# swift-nav.net
KiCad netlist of a schematic drawn in EAGLE
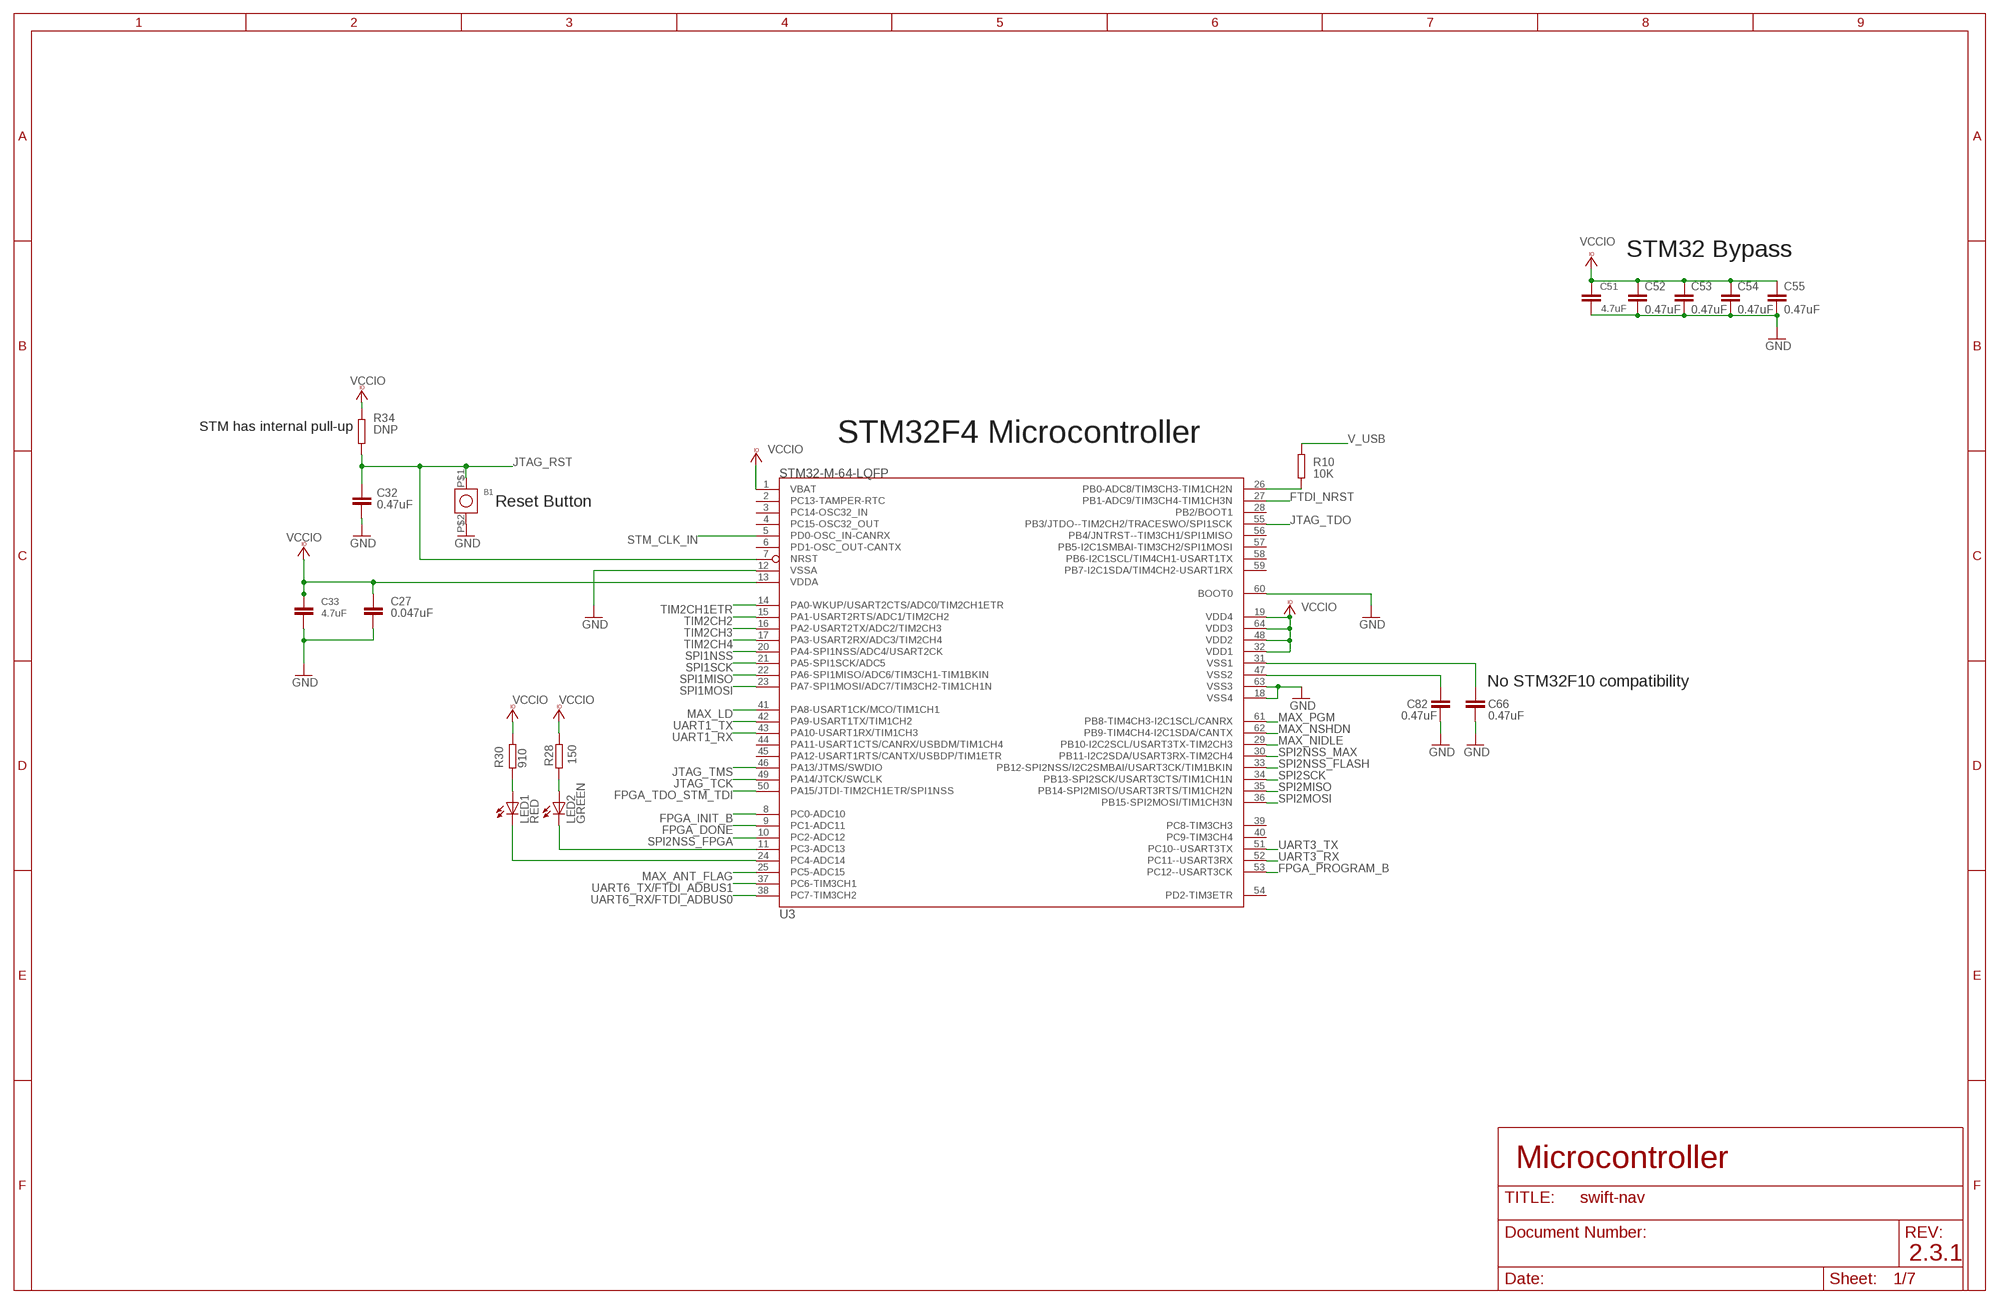
[diagram p0: schematic, sheet 1]
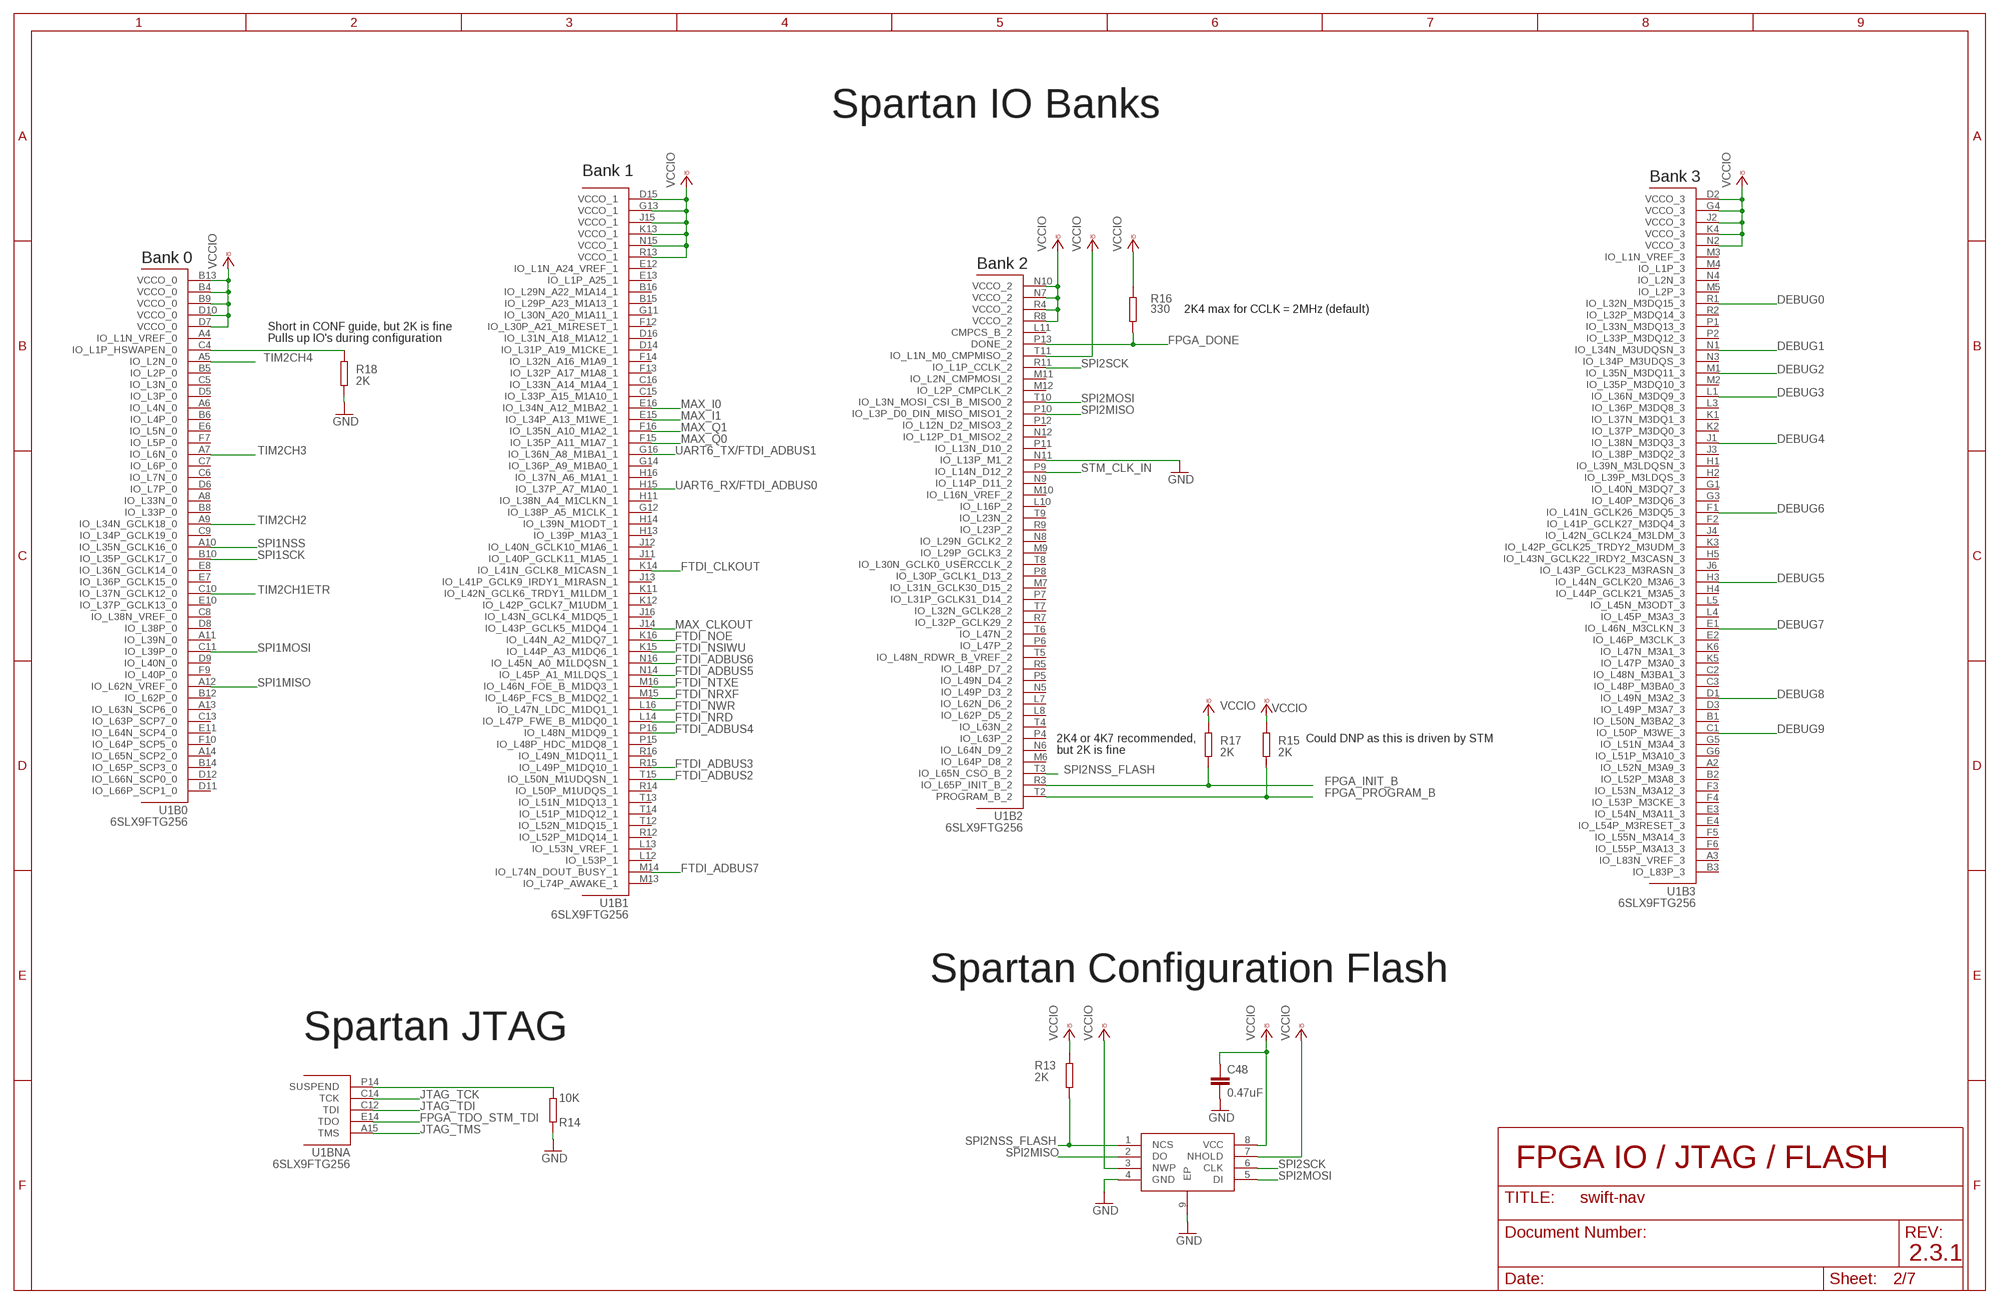
[diagram p1: schematic, sheet 2]
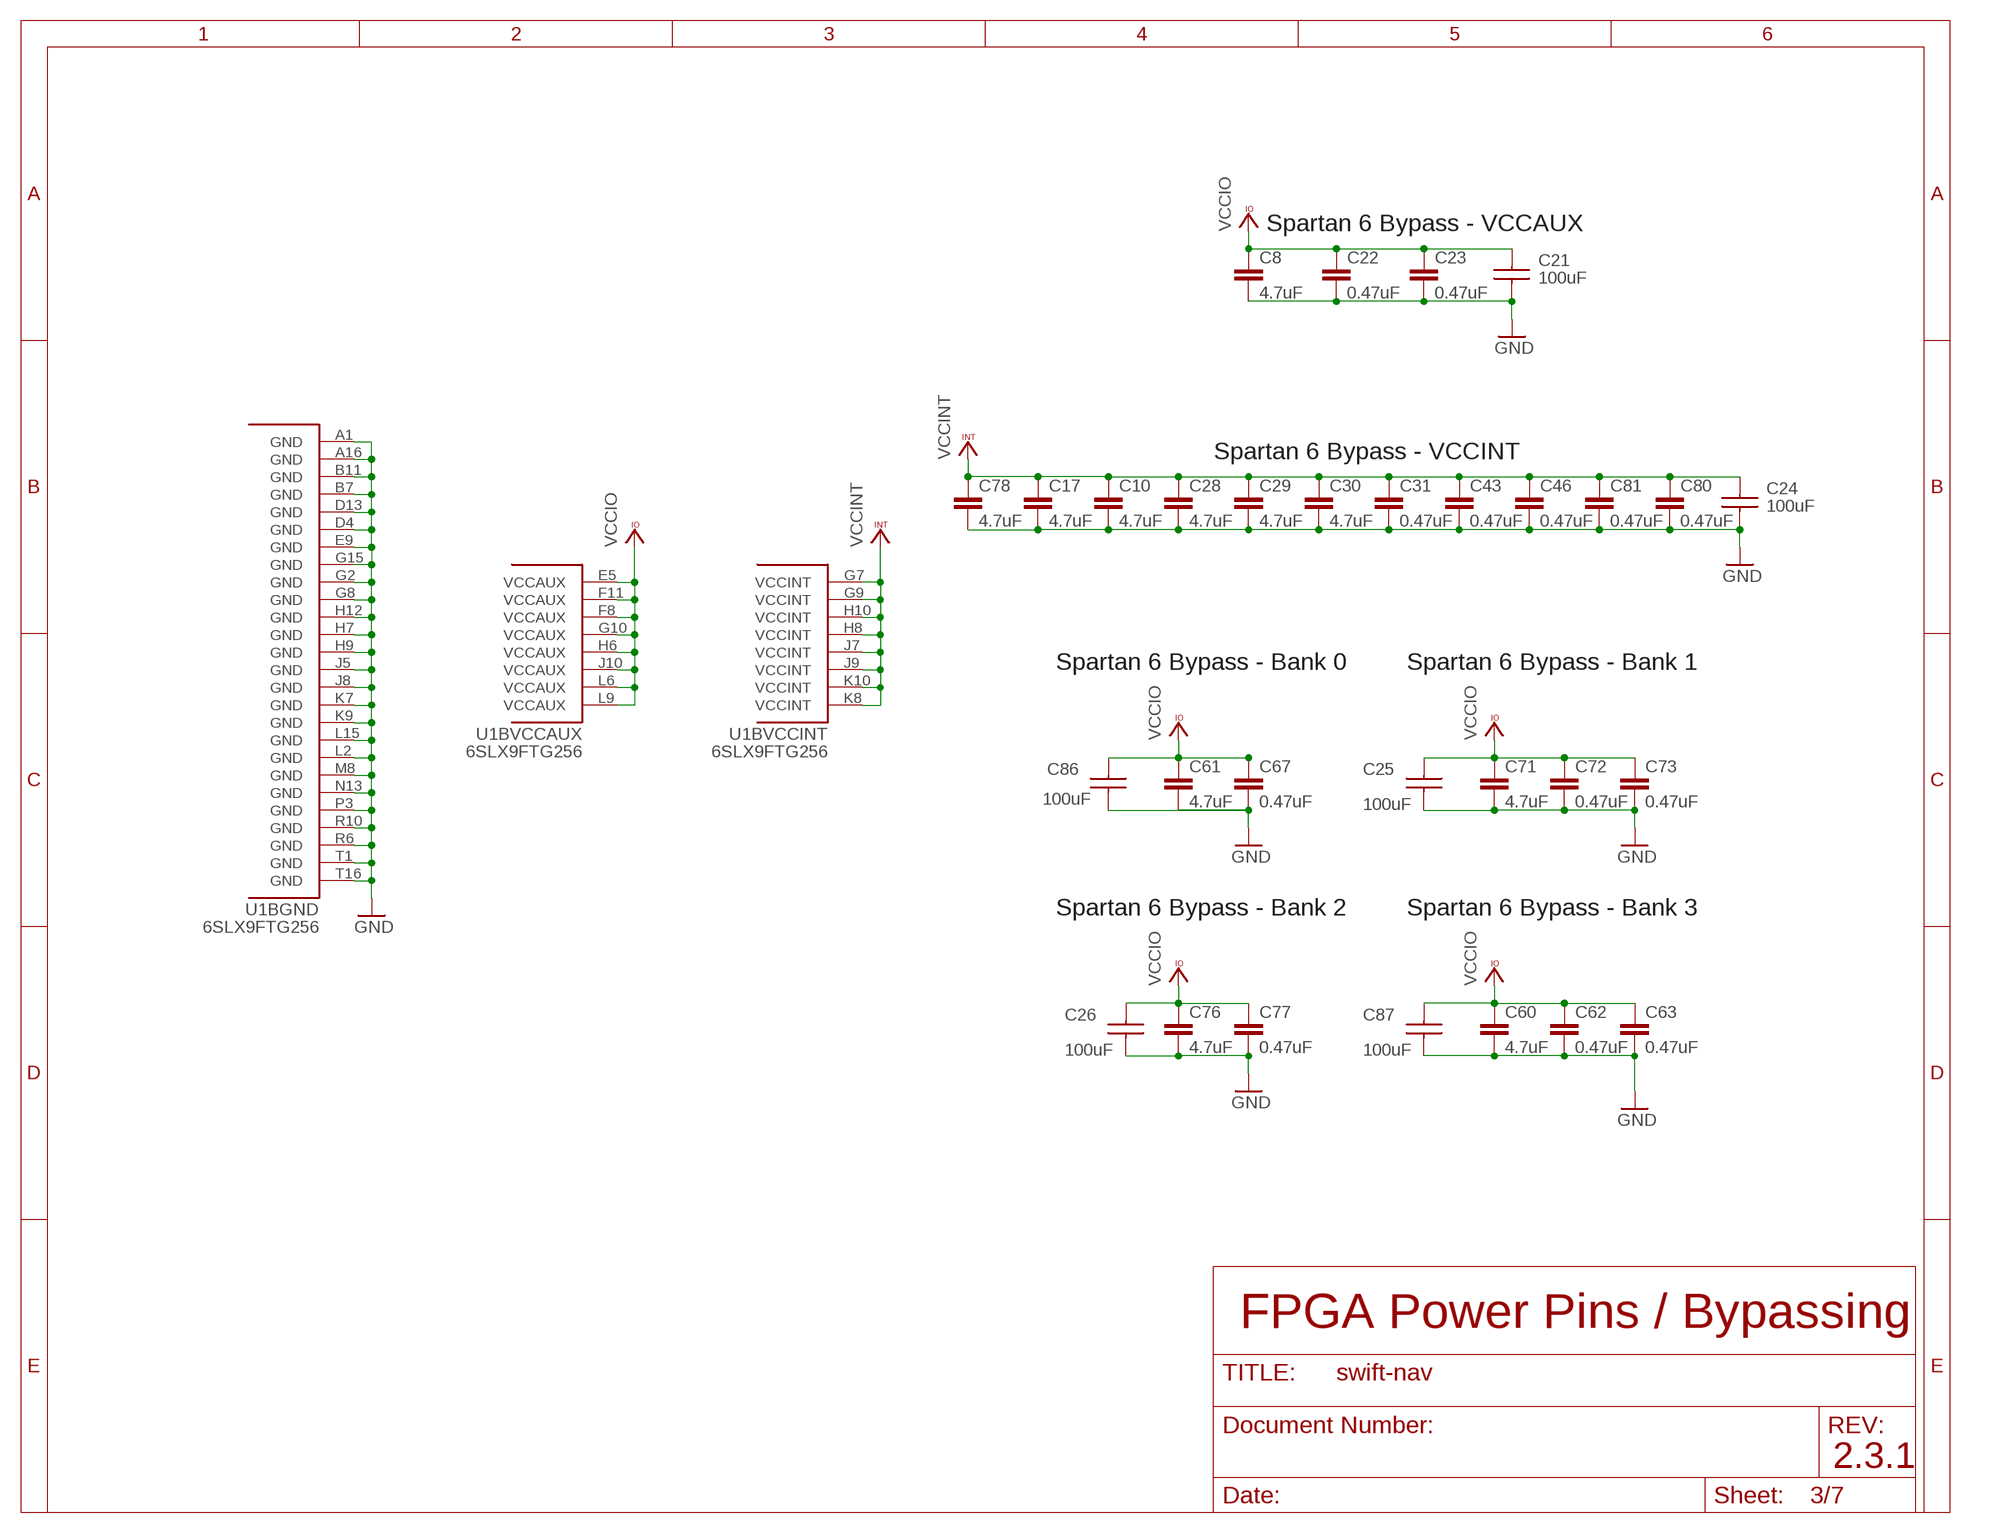
[diagram p2: schematic, sheet 3]
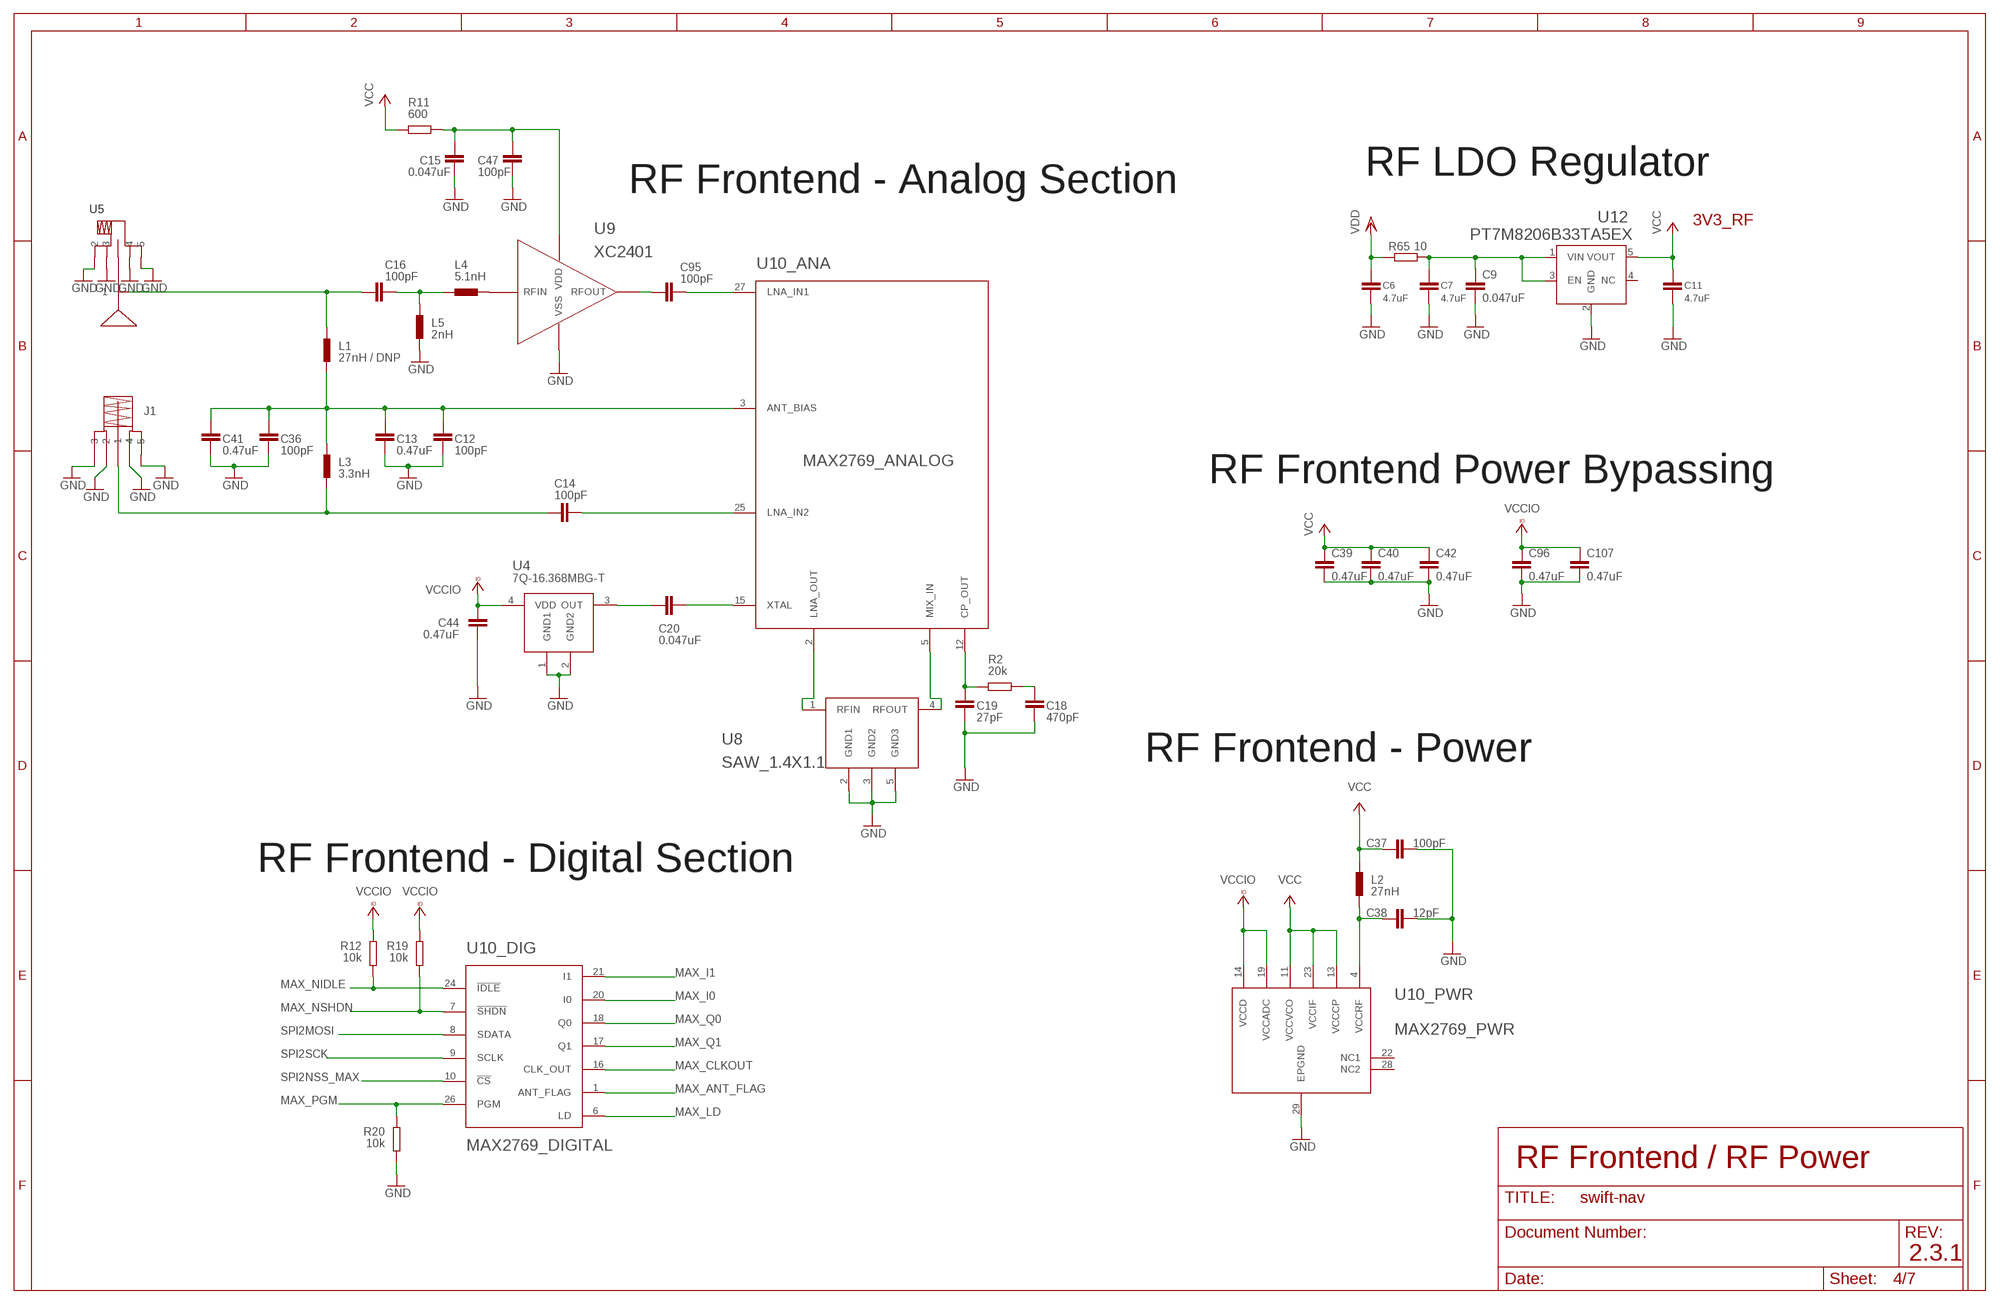
[diagram p3: schematic, sheet 4]
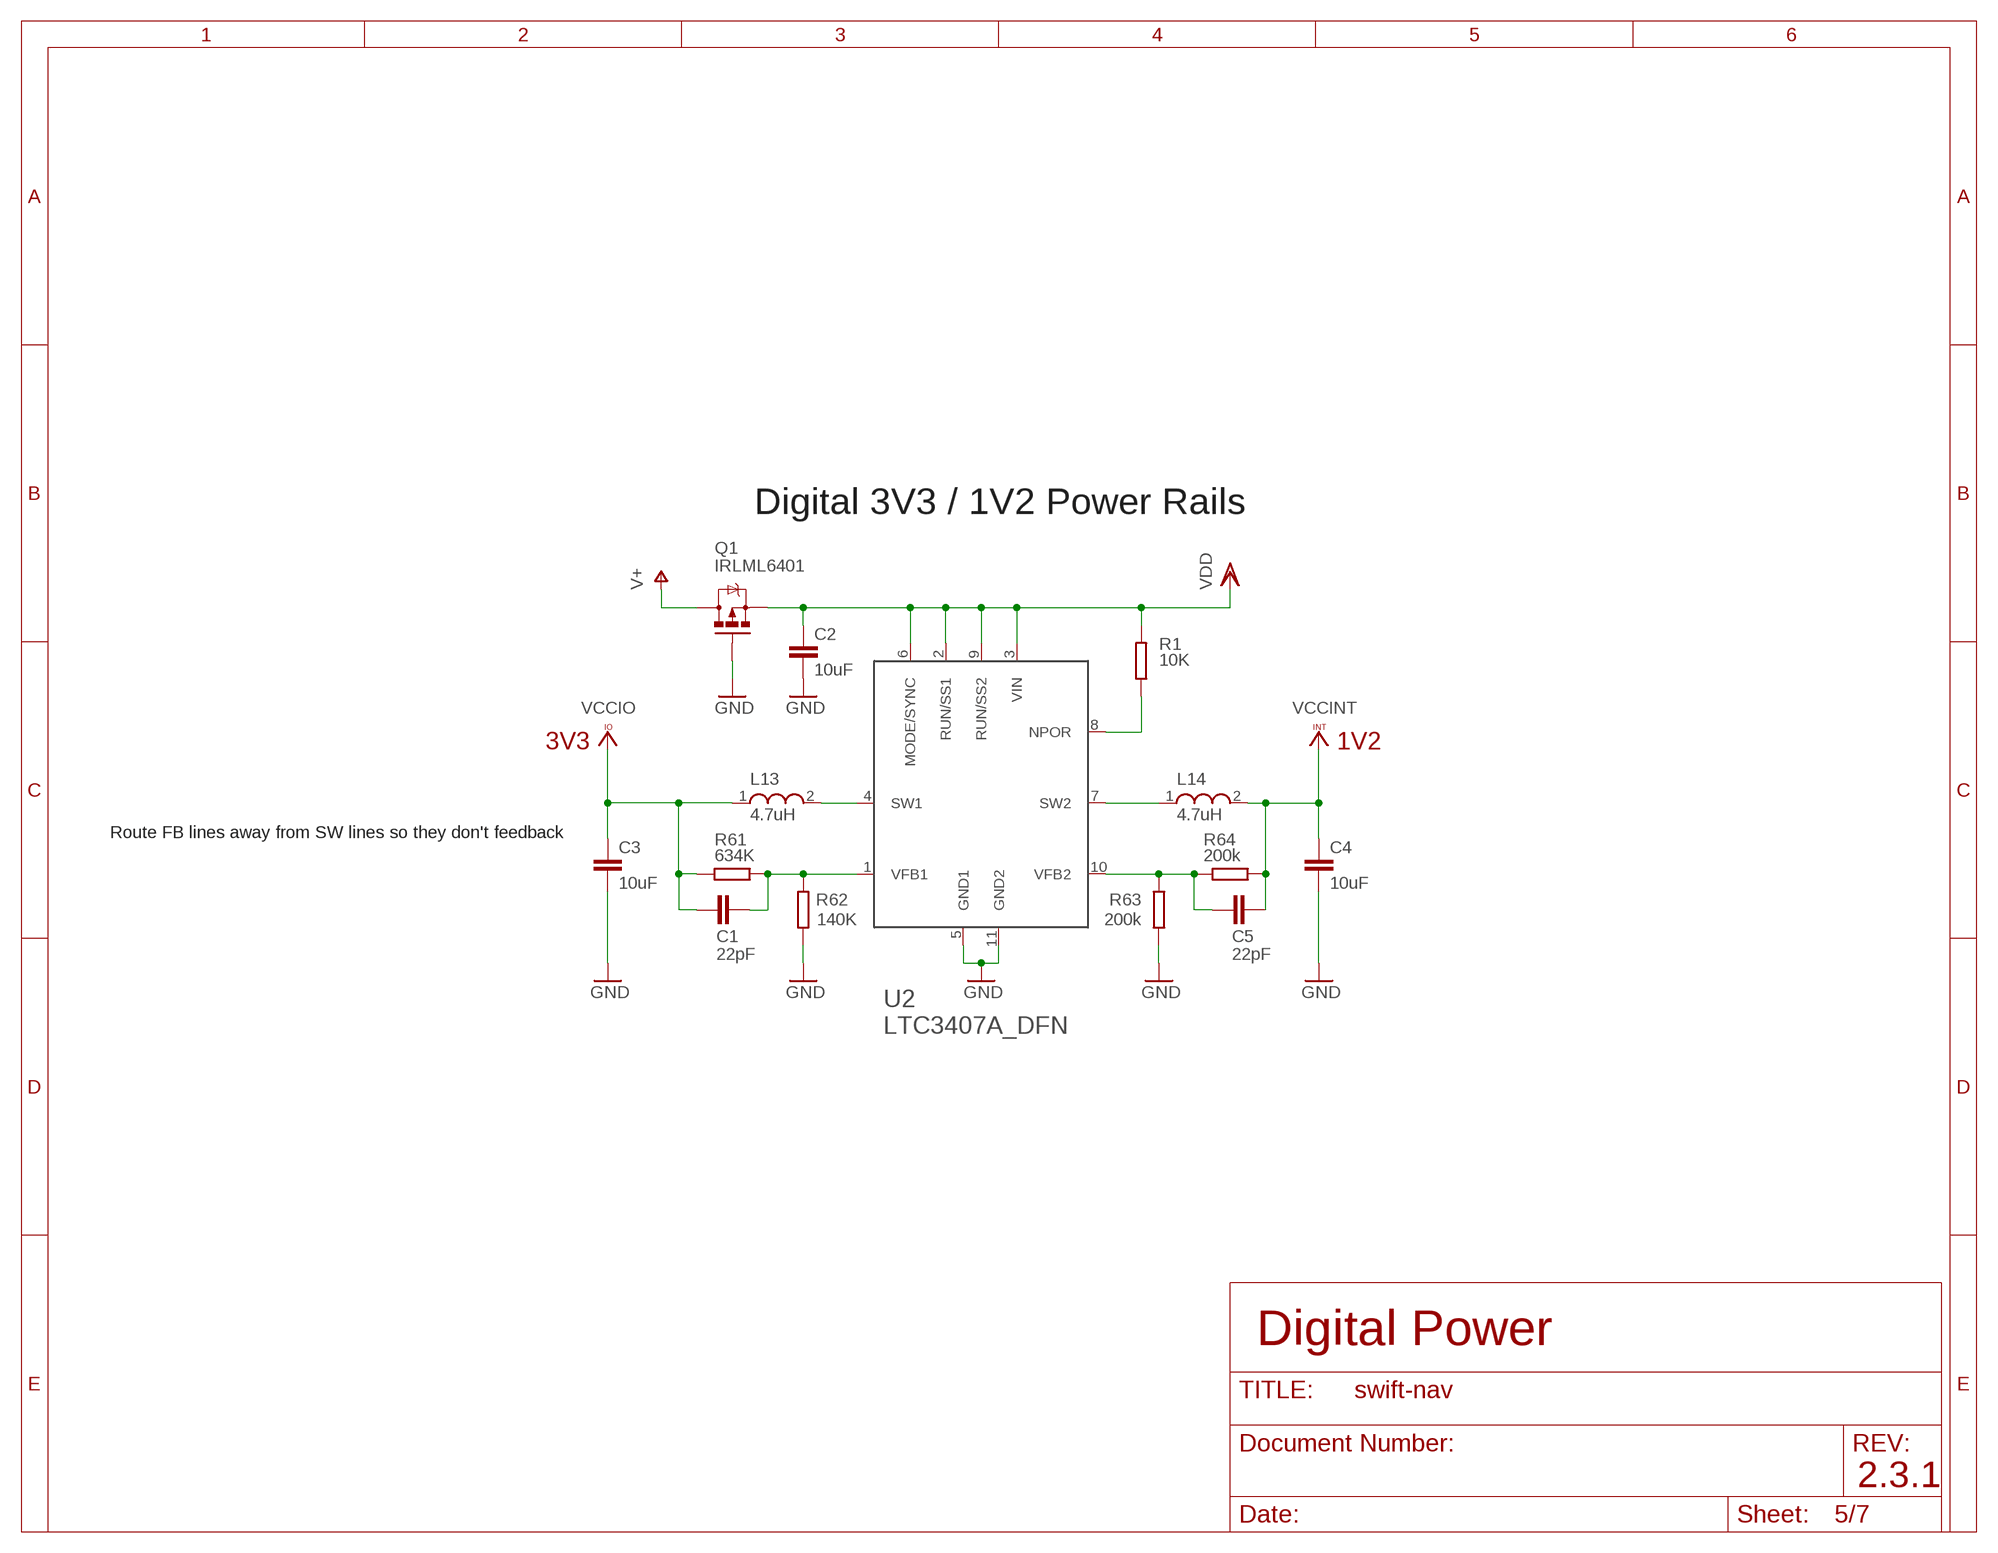
[diagram p4: schematic, sheet 5]
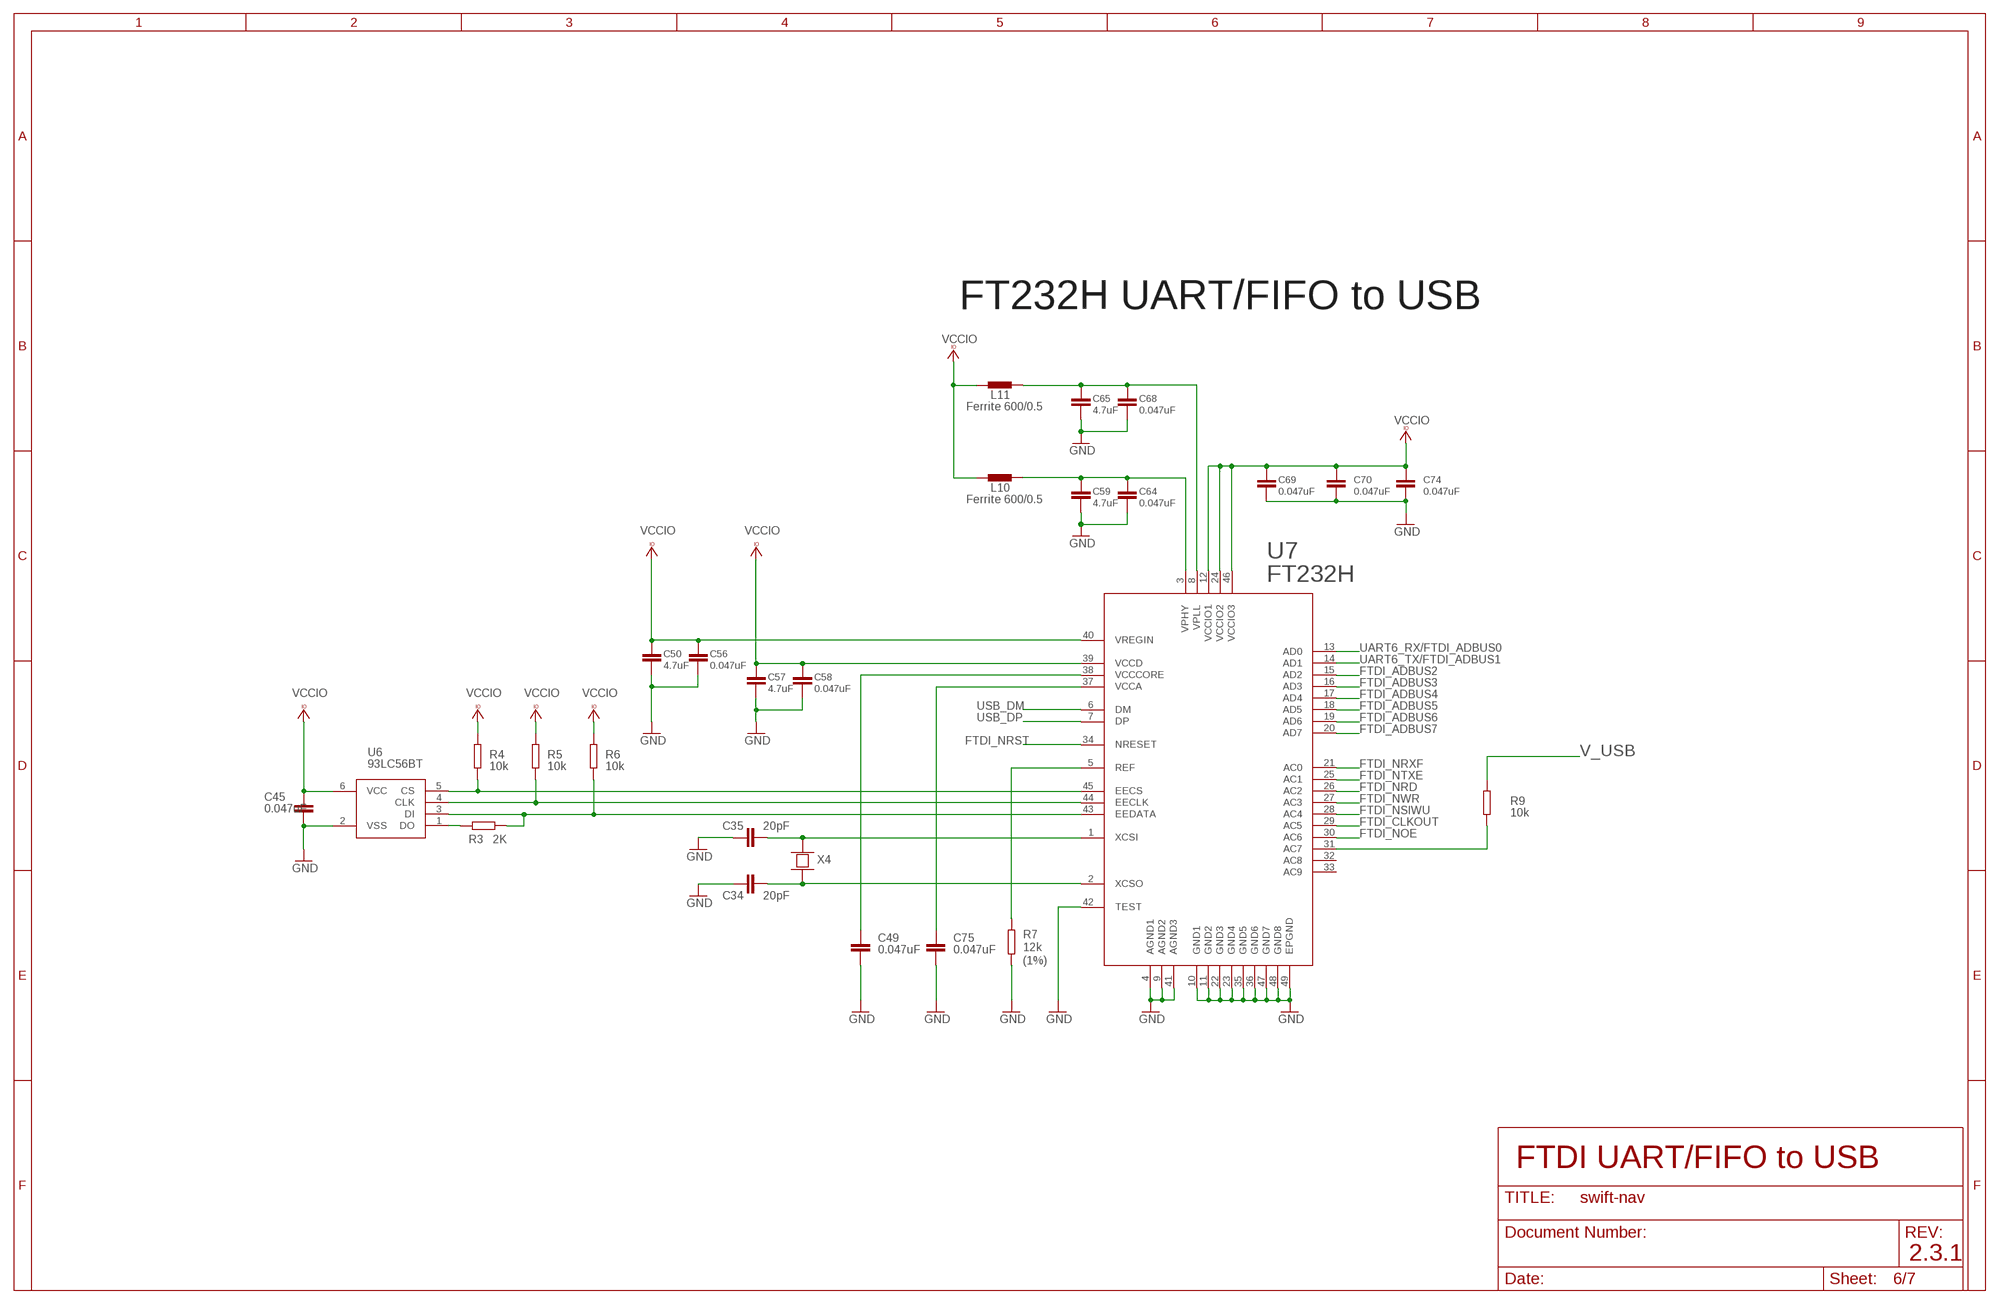
[diagram p5: schematic, sheet 6]
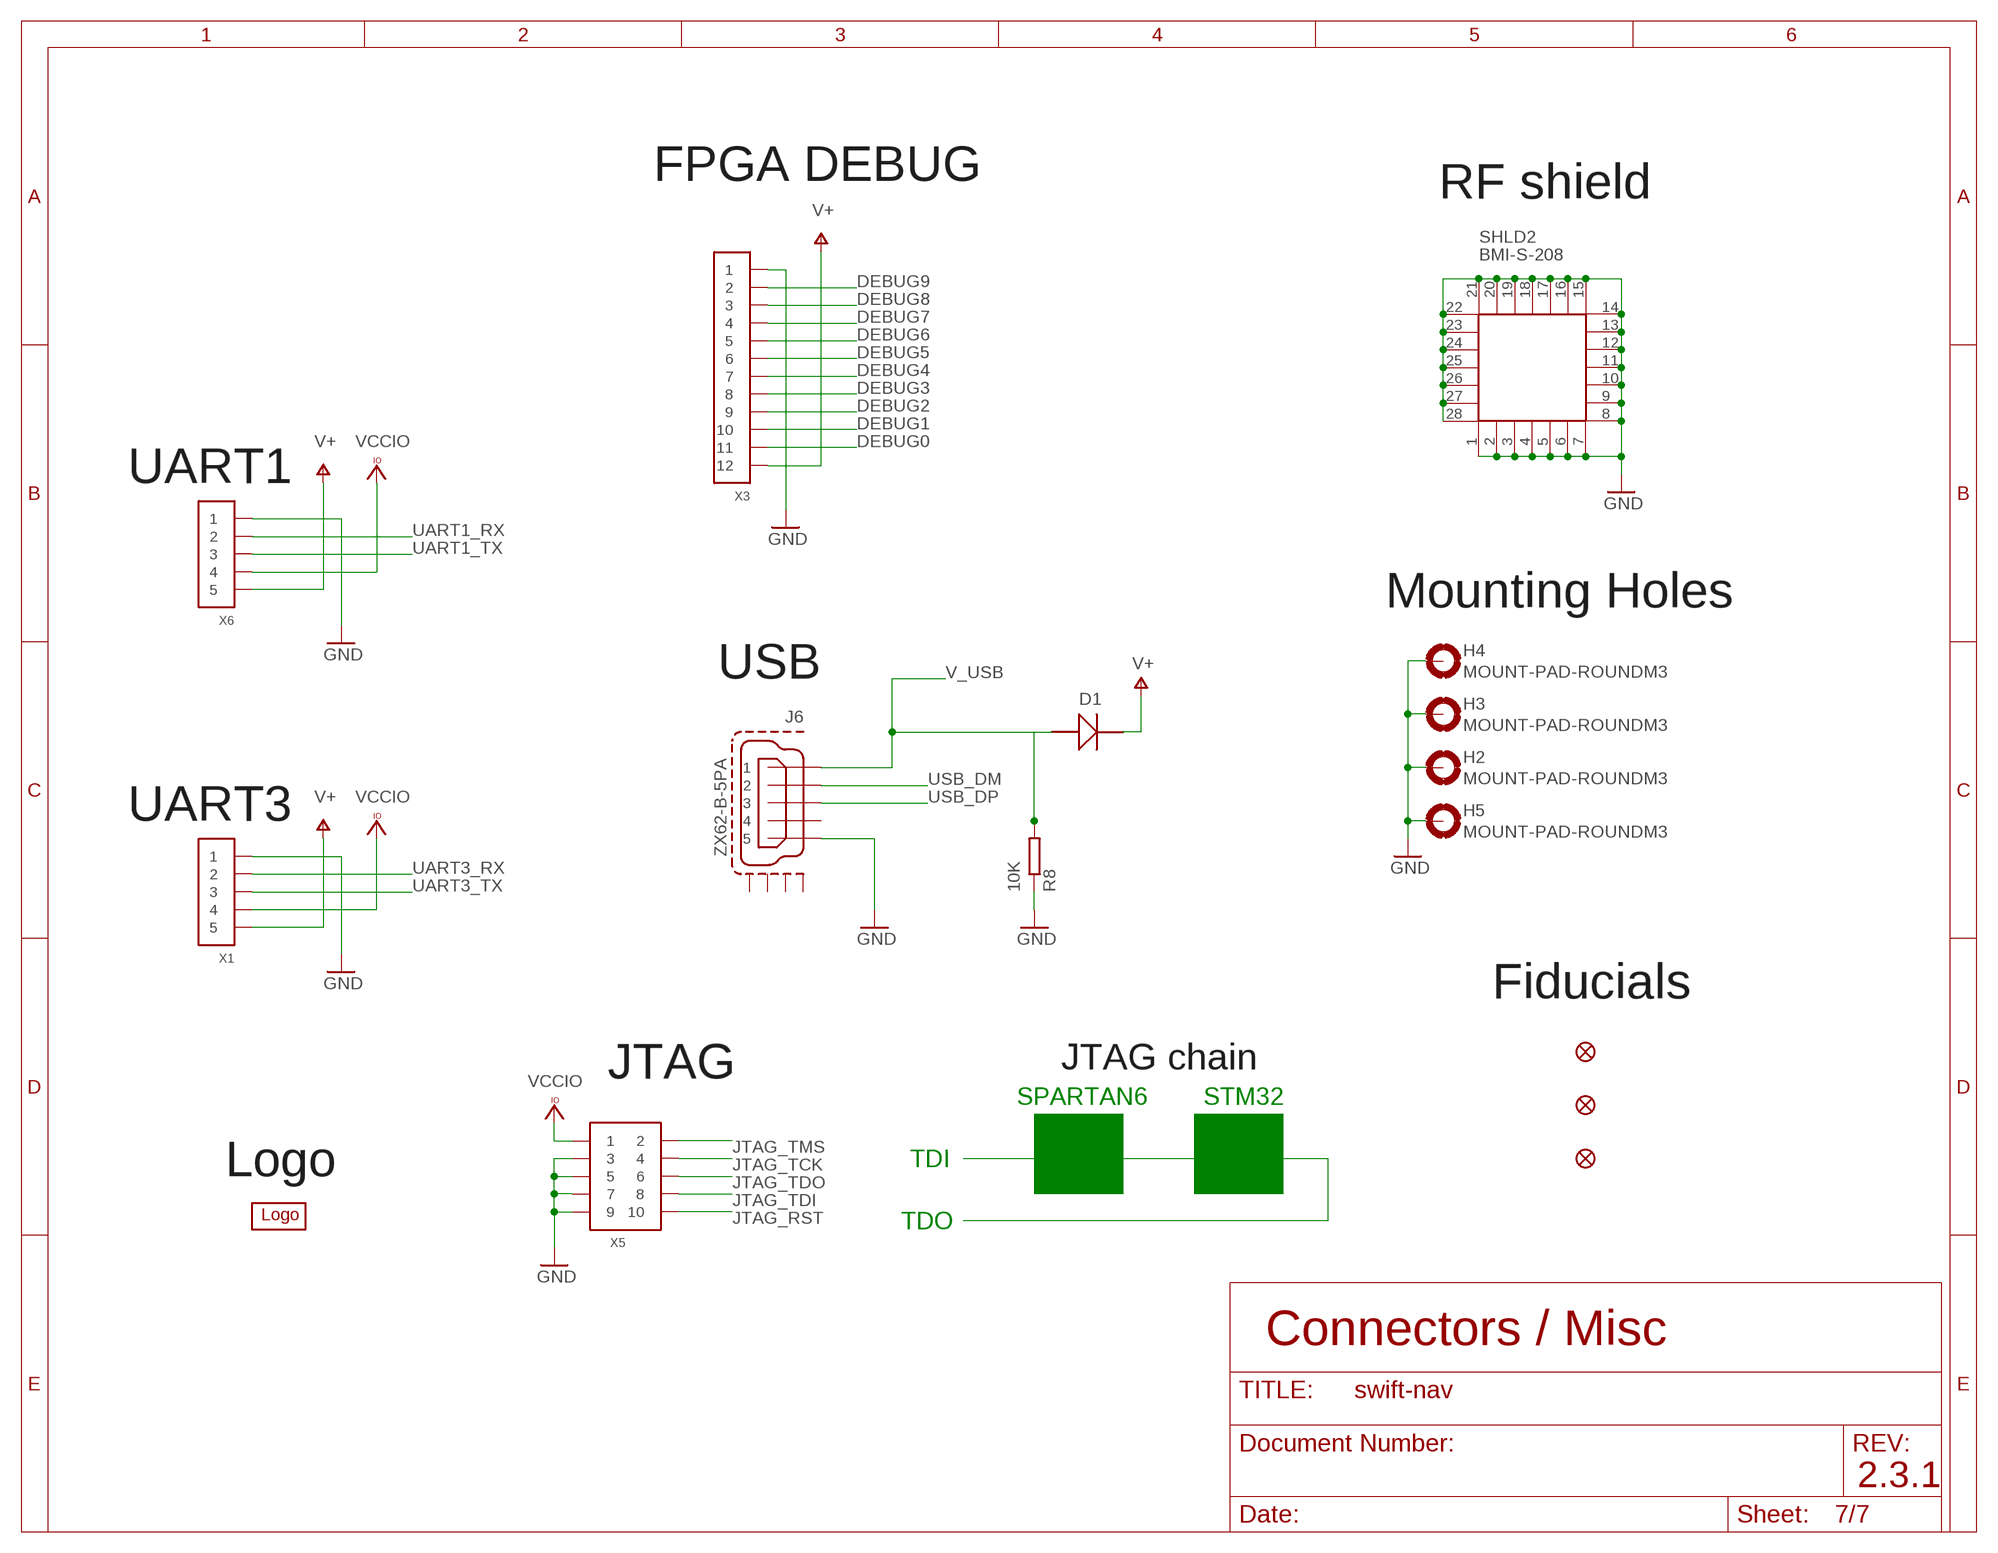
[diagram p6: schematic, sheet 7]

(export (version "E")
  (design (tool "Eeschema 10.0.6"))
  (components
    (comp (ref "C8")
      (value "4.7uF")
      (footprint "eagle-import:0603-CAP")
      (libsource (lib "eagle-import") (part "CAPACITOR-0603"))
    )
    (comp (ref "C10")
      (value "4.7uF")
      (footprint "eagle-import:0603-CAP")
      (libsource (lib "eagle-import") (part "CAPACITOR-0603"))
    )
    (comp (ref "C17")
      (value "4.7uF")
      (footprint "eagle-import:0603-CAP")
      (libsource (lib "eagle-import") (part "CAPACITOR-0603"))
    )
    (comp (ref "C21")
      (value "100uF")
      (footprint "eagle-import:C1210")
      (libsource (lib "eagle-import") (part "C1210"))
    )
    (comp (ref "C22")
      (value "0.47uF")
      (footprint "eagle-import:0402-CAP")
      (libsource (lib "eagle-import") (part "CAPACITOR-0402"))
    )
    (comp (ref "C23")
      (value "0.47uF")
      (footprint "eagle-import:0402-CAP")
      (libsource (lib "eagle-import") (part "CAPACITOR-0402"))
    )
    (comp (ref "C24")
      (value "100uF")
      (footprint "eagle-import:C1210")
      (libsource (lib "eagle-import") (part "C1210"))
    )
    (comp (ref "C25")
      (value "100uF")
      (footprint "eagle-import:C1210")
      (libsource (lib "eagle-import") (part "C1210"))
    )
    (comp (ref "C26")
      (value "100uF")
      (footprint "eagle-import:C1210")
      (libsource (lib "eagle-import") (part "C1210"))
    )
    (comp (ref "C28")
      (value "4.7uF")
      (footprint "eagle-import:0603-CAP")
      (libsource (lib "eagle-import") (part "CAPACITOR-0603"))
    )
    (comp (ref "C29")
      (value "4.7uF")
      (footprint "eagle-import:0603-CAP")
      (libsource (lib "eagle-import") (part "CAPACITOR-0603"))
    )
    (comp (ref "C30")
      (value "4.7uF")
      (footprint "eagle-import:0603-CAP")
      (libsource (lib "eagle-import") (part "CAPACITOR-0603"))
    )
    (comp (ref "C31")
      (value "0.47uF")
      (footprint "eagle-import:0402-CAP")
      (libsource (lib "eagle-import") (part "CAPACITOR-0402"))
    )
    (comp (ref "C43")
      (value "0.47uF")
      (footprint "eagle-import:0402-CAP")
      (libsource (lib "eagle-import") (part "CAPACITOR-0402"))
    )
    (comp (ref "C46")
      (value "0.47uF")
      (footprint "eagle-import:0402-CAP")
      (libsource (lib "eagle-import") (part "CAPACITOR-0402"))
    )
    (comp (ref "C60")
      (value "4.7uF")
      (footprint "eagle-import:0603-CAP")
      (libsource (lib "eagle-import") (part "CAPACITOR-0603"))
    )
    (comp (ref "C61")
      (value "4.7uF")
      (footprint "eagle-import:0603-CAP")
      (libsource (lib "eagle-import") (part "CAPACITOR-0603"))
    )
    (comp (ref "C62")
      (value "0.47uF")
      (footprint "eagle-import:0402-CAP")
      (libsource (lib "eagle-import") (part "CAPACITOR-0402"))
    )
    (comp (ref "C63")
      (value "0.47uF")
      (footprint "eagle-import:0402-CAP")
      (libsource (lib "eagle-import") (part "CAPACITOR-0402"))
    )
    (comp (ref "C67")
      (value "0.47uF")
      (footprint "eagle-import:0402-CAP")
      (libsource (lib "eagle-import") (part "CAPACITOR-0402"))
    )
    (comp (ref "C71")
      (value "4.7uF")
      (footprint "eagle-import:0603-CAP")
      (libsource (lib "eagle-import") (part "CAPACITOR-0603"))
    )
    (comp (ref "C72")
      (value "0.47uF")
      (footprint "eagle-import:0402-CAP")
      (libsource (lib "eagle-import") (part "CAPACITOR-0402"))
    )
    (comp (ref "C73")
      (value "0.47uF")
      (footprint "eagle-import:0402-CAP")
      (libsource (lib "eagle-import") (part "CAPACITOR-0402"))
    )
    (comp (ref "C76")
      (value "4.7uF")
      (footprint "eagle-import:0603-CAP")
      (libsource (lib "eagle-import") (part "CAPACITOR-0603"))
    )
    (comp (ref "C77")
      (value "0.47uF")
      (footprint "eagle-import:0402-CAP")
      (libsource (lib "eagle-import") (part "CAPACITOR-0402"))
    )
    (comp (ref "C78")
      (value "4.7uF")
      (footprint "eagle-import:0603-CAP")
      (libsource (lib "eagle-import") (part "CAPACITOR-0603"))
    )
    (comp (ref "C80")
      (value "0.47uF")
      (footprint "eagle-import:0402-CAP")
      (libsource (lib "eagle-import") (part "CAPACITOR-0402"))
    )
    (comp (ref "C81")
      (value "0.47uF")
      (footprint "eagle-import:0402-CAP")
      (libsource (lib "eagle-import") (part "CAPACITOR-0402"))
    )
    (comp (ref "C86")
      (value "100uF")
      (footprint "eagle-import:C1210")
      (libsource (lib "eagle-import") (part "C1210"))
    )
    (comp (ref "C87")
      (value "100uF")
      (footprint "eagle-import:C1210")
      (libsource (lib "eagle-import") (part "C1210"))
    )
    (comp (ref "U1")
      (value "6SLX9FTG256")
      (footprint "eagle-import:FT256")
      (libsource (lib "eagle-import") (part "6SLX9FTG256"))
    )
    (comp (ref "C6")
      (value "4.7uF")
      (footprint "eagle-import:0603-CAP")
      (libsource (lib "eagle-import") (part "CAPACITOR-0603"))
    )
    (comp (ref "C7")
      (value "4.7uF")
      (footprint "eagle-import:0603-CAP")
      (libsource (lib "eagle-import") (part "CAPACITOR-0603"))
    )
    (comp (ref "C9")
      (value "0.047uF")
      (footprint "eagle-import:0402-CAP")
      (libsource (lib "eagle-import") (part "CAPACITOR-0402"))
    )
    (comp (ref "C11")
      (value "4.7uF")
      (footprint "eagle-import:0603-CAP")
      (libsource (lib "eagle-import") (part "CAPACITOR-0603"))
    )
    (comp (ref "C12")
      (value "100pF")
      (footprint "eagle-import:0402-CAP")
      (libsource (lib "eagle-import") (part "CAPACITOR-0402"))
    )
    (comp (ref "C13")
      (value "0.47uF")
      (footprint "eagle-import:0402-CAP")
      (libsource (lib "eagle-import") (part "CAPACITOR-0402"))
    )
    (comp (ref "C14")
      (value "100pF")
      (footprint "eagle-import:0402-CAP")
      (libsource (lib "eagle-import") (part "CAPACITOR-0402"))
    )
    (comp (ref "C15")
      (value "0.047uF")
      (footprint "eagle-import:0402-CAP")
      (libsource (lib "eagle-import") (part "CAPACITOR-0402"))
    )
    (comp (ref "C16")
      (value "100pF")
      (footprint "eagle-import:0402-CAP")
      (libsource (lib "eagle-import") (part "CAPACITOR-0402"))
    )
    (comp (ref "C18")
      (value "470pF")
      (footprint "eagle-import:0402-CAP")
      (libsource (lib "eagle-import") (part "CAPACITOR-0402"))
    )
    (comp (ref "C19")
      (value "27pF")
      (footprint "eagle-import:0402-CAP")
      (libsource (lib "eagle-import") (part "CAPACITOR-0402"))
    )
    (comp (ref "C20")
      (value "0.047uF")
      (footprint "eagle-import:0402-CAP")
      (libsource (lib "eagle-import") (part "CAPACITOR-0402"))
    )
    (comp (ref "C36")
      (value "100pF")
      (footprint "eagle-import:0402-CAP")
      (libsource (lib "eagle-import") (part "CAPACITOR-0402"))
    )
    (comp (ref "C37")
      (value "100pF")
      (footprint "eagle-import:0402-CAP")
      (libsource (lib "eagle-import") (part "CAPACITOR-0402"))
    )
    (comp (ref "C38")
      (value "12pF")
      (footprint "eagle-import:0402-CAP")
      (libsource (lib "eagle-import") (part "CAPACITOR-0402"))
    )
    (comp (ref "C39")
      (value "0.47uF")
      (footprint "eagle-import:0402-CAP")
      (libsource (lib "eagle-import") (part "CAPACITOR-0402"))
    )
    (comp (ref "C40")
      (value "0.47uF")
      (footprint "eagle-import:0402-CAP")
      (libsource (lib "eagle-import") (part "CAPACITOR-0402"))
    )
    (comp (ref "C41")
      (value "0.47uF")
      (footprint "eagle-import:0402-CAP")
      (libsource (lib "eagle-import") (part "CAPACITOR-0402"))
    )
    (comp (ref "C42")
      (value "0.47uF")
      (footprint "eagle-import:0402-CAP")
      (libsource (lib "eagle-import") (part "CAPACITOR-0402"))
    )
    (comp (ref "C44")
      (value "0.47uF")
      (footprint "eagle-import:0402-CAP")
      (libsource (lib "eagle-import") (part "CAPACITOR-0402"))
    )
    (comp (ref "C47")
      (value "100pF")
      (footprint "eagle-import:0402-CAP")
      (libsource (lib "eagle-import") (part "CAPACITOR-0402"))
    )
    (comp (ref "C95")
      (value "100pF")
      (footprint "eagle-import:0402-CAP")
      (libsource (lib "eagle-import") (part "CAPACITOR-0402"))
    )
    (comp (ref "C96")
      (value "0.47uF")
      (footprint "eagle-import:0402-CAP")
      (libsource (lib "eagle-import") (part "CAPACITOR-0402"))
    )
    (comp (ref "C107")
      (value "0.47uF")
      (footprint "eagle-import:0402-CAP")
      (libsource (lib "eagle-import") (part "CAPACITOR-0402"))
    )
    (comp (ref "J1")
      (value "SMA_EDGE")
      (footprint "eagle-import:SMA_EDGE")
      (libsource (lib "eagle-import") (part "SMA_EDGE"))
    )
    (comp (ref "L1")
      (value "27nH / DNP")
      (footprint "eagle-import:0402-IND")
      (libsource (lib "eagle-import") (part "INDUCTOR-0402"))
    )
    (comp (ref "L2")
      (value "27nH")
      (footprint "eagle-import:0402-IND")
      (libsource (lib "eagle-import") (part "INDUCTOR-0402"))
    )
    (comp (ref "L3")
      (value "3.3nH")
      (footprint "eagle-import:0402-IND")
      (libsource (lib "eagle-import") (part "INDUCTOR-0402"))
    )
    (comp (ref "L4")
      (value "5.1nH")
      (footprint "eagle-import:0402-IND")
      (libsource (lib "eagle-import") (part "INDUCTOR-0402"))
    )
    (comp (ref "L5")
      (value "2nH")
      (footprint "eagle-import:0402-IND")
      (libsource (lib "eagle-import") (part "INDUCTOR-0402"))
    )
    (comp (ref "R2")
      (value "20k")
      (footprint "eagle-import:0402-RES")
      (libsource (lib "eagle-import") (part "RESISTOR-0402"))
    )
    (comp (ref "R11")
      (value "600")
      (footprint "eagle-import:0402-RES")
      (libsource (lib "eagle-import") (part "RESISTOR-0402"))
    )
    (comp (ref "R12")
      (value "10k")
      (footprint "eagle-import:0402-RES")
      (libsource (lib "eagle-import") (part "RESISTOR-0402"))
    )
    (comp (ref "R19")
      (value "10k")
      (footprint "eagle-import:0402-RES")
      (libsource (lib "eagle-import") (part "RESISTOR-0402"))
    )
    (comp (ref "R20")
      (value "10k")
      (footprint "eagle-import:0402-RES")
      (libsource (lib "eagle-import") (part "RESISTOR-0402"))
    )
    (comp (ref "R65")
      (value "10")
      (footprint "eagle-import:0402-RES")
      (libsource (lib "eagle-import") (part "RESISTOR-0402"))
    )
    (comp (ref "U4")
      (value "7Q-16.368MBG-T")
      (footprint "eagle-import:TCX_7Q")
      (libsource (lib "eagle-import") (part "7Q-16.368MBG-T"))
    )
    (comp (ref "U5")
      (value "SMA_PATCH_SMDGND")
      (footprint "eagle-import:SMA_PATCH_SMDGND")
      (libsource (lib "eagle-import") (part "SMA_PATCH_SMDGND"))
    )
    (comp (ref "U8")
      (value "SAW_1.4X1.1")
      (footprint "eagle-import:SAW_1.4X1.1")
      (libsource (lib "eagle-import") (part "SAW_1.4X1.1"))
    )
    (comp (ref "U9")
      (value "XC2401")
      (footprint "eagle-import:XC2401")
      (libsource (lib "eagle-import") (part "XC2401"))
    )
    (comp (ref "U10")
      (value "MAX2769")
      (footprint "eagle-import:MAX2769")
      (libsource (lib "eagle-import") (part "MAX2769"))
    )
    (comp (ref "U12")
      (value "PT7M8206B33TA5EX")
      (footprint "eagle-import:PT7M8206B33TA5EX")
      (libsource (lib "eagle-import") (part "PT7M8206B33TA5EX"))
    )
    (comp (ref "B1")
      (value "B3U-1000P")
      (footprint "eagle-import:B3U-1000P")
      (libsource (lib "eagle-import") (part "B3U-1000P"))
    )
    (comp (ref "C27")
      (value "0.047uF")
      (footprint "eagle-import:0402-CAP")
      (libsource (lib "eagle-import") (part "CAPACITOR-0402"))
    )
    (comp (ref "C32")
      (value "0.47uF")
      (footprint "eagle-import:0402-CAP")
      (libsource (lib "eagle-import") (part "CAPACITOR-0402"))
    )
    (comp (ref "C33")
      (value "4.7uF")
      (footprint "eagle-import:0603-CAP")
      (libsource (lib "eagle-import") (part "CAPACITOR-0603"))
    )
    (comp (ref "C51")
      (value "4.7uF")
      (footprint "eagle-import:0603-CAP")
      (libsource (lib "eagle-import") (part "CAPACITOR-0603"))
    )
    (comp (ref "C52")
      (value "0.47uF")
      (footprint "eagle-import:0402-CAP")
      (libsource (lib "eagle-import") (part "CAPACITOR-0402"))
    )
    (comp (ref "C53")
      (value "0.47uF")
      (footprint "eagle-import:0402-CAP")
      (libsource (lib "eagle-import") (part "CAPACITOR-0402"))
    )
    (comp (ref "C54")
      (value "0.47uF")
      (footprint "eagle-import:0402-CAP")
      (libsource (lib "eagle-import") (part "CAPACITOR-0402"))
    )
    (comp (ref "C55")
      (value "0.47uF")
      (footprint "eagle-import:0402-CAP")
      (libsource (lib "eagle-import") (part "CAPACITOR-0402"))
    )
    (comp (ref "C66")
      (value "0.47uF")
      (footprint "eagle-import:0402-CAP")
      (libsource (lib "eagle-import") (part "CAPACITOR-0402"))
    )
    (comp (ref "C82")
      (value "0.47uF")
      (footprint "eagle-import:0402-CAP")
      (libsource (lib "eagle-import") (part "CAPACITOR-0402"))
    )
    (comp (ref "LED1")
      (value "RED")
      (footprint "eagle-import:0603-LED")
      (libsource (lib "eagle-import") (part "LED-0603"))
    )
    (comp (ref "LED2")
      (value "GREEN")
      (footprint "eagle-import:0603-LED")
      (libsource (lib "eagle-import") (part "LED-0603"))
    )
    (comp (ref "R10")
      (value "10K")
      (footprint "eagle-import:0402-RES")
      (libsource (lib "eagle-import") (part "RESISTOR-0402"))
    )
    (comp (ref "R28")
      (value "150")
      (footprint "eagle-import:0402-RES")
      (libsource (lib "eagle-import") (part "RESISTOR-0402"))
    )
    (comp (ref "R30")
      (value "910")
      (footprint "eagle-import:0402-RES")
      (libsource (lib "eagle-import") (part "RESISTOR-0402"))
    )
    (comp (ref "R34")
      (value "DNP")
      (footprint "eagle-import:0402-RES")
      (libsource (lib "eagle-import") (part "RESISTOR-0402"))
    )
    (comp (ref "U3")
      (value "STM32-M-64-LQFP")
      (footprint "eagle-import:LQFP64")
      (libsource (lib "eagle-import") (part "STM32-M-64-LQFP"))
    )
    (comp (ref "D1")
      (value "MBR0520")
      (footprint "eagle-import:SOD-123")
      (libsource (lib "eagle-import") (part "MBR0520"))
    )
    (comp (ref "H2")
      (value "MOUNT-PAD-ROUNDM3")
      (footprint "eagle-import:M3-PAD")
      (libsource (lib "eagle-import") (part "MOUNT-PAD-ROUNDM3"))
    )
    (comp (ref "H3")
      (value "MOUNT-PAD-ROUNDM3")
      (footprint "eagle-import:M3-PAD")
      (libsource (lib "eagle-import") (part "MOUNT-PAD-ROUNDM3"))
    )
    (comp (ref "H4")
      (value "MOUNT-PAD-ROUNDM3")
      (footprint "eagle-import:M3-PAD")
      (libsource (lib "eagle-import") (part "MOUNT-PAD-ROUNDM3"))
    )
    (comp (ref "H5")
      (value "MOUNT-PAD-ROUNDM3")
      (footprint "eagle-import:M3-PAD")
      (libsource (lib "eagle-import") (part "MOUNT-PAD-ROUNDM3"))
    )
    (comp (ref "J6")
      (value "ZX62-B-5PA")
      (footprint "eagle-import:ZX62-B-5PA")
      (libsource (lib "eagle-import") (part "ZX62-B-5PA"))
    )
    (comp (ref "JP8")
      (value "FIDUCIAL1.5X3")
      (footprint "eagle-import:FIDUCIAL-1.5X3")
      (libsource (lib "eagle-import") (part "FIDUCIAL1.5X3"))
    )
    (comp (ref "JP9")
      (value "FIDUCIAL1.5X3")
      (footprint "eagle-import:FIDUCIAL-1.5X3")
      (libsource (lib "eagle-import") (part "FIDUCIAL1.5X3"))
    )
    (comp (ref "JP10")
      (value "FIDUCIAL1.5X3")
      (footprint "eagle-import:FIDUCIAL-1.5X3")
      (libsource (lib "eagle-import") (part "FIDUCIAL1.5X3"))
    )
    (comp (ref "R8")
      (value "10K")
      (footprint "eagle-import:0402-RES")
      (libsource (lib "eagle-import") (part "RESISTOR-0402"))
    )
    (comp (ref "SHLD2")
      (value "BMI-S-208")
      (footprint "eagle-import:BMI-S-208")
      (libsource (lib "eagle-import") (part "BMI-S-208"))
    )
    (comp (ref "U$2")
      (value "LOGOLOGO3_SMALL")
      (footprint "eagle-import:LOGO3_SMALL")
      (libsource (lib "eagle-import") (part "LOGOLOGO3_SMALL"))
    )
    (comp (ref "X1")
      (value "CONN_5-1-53261")
      (footprint "eagle-import:PB-53261-05")
      (libsource (lib "eagle-import") (part "CONN_5-1-53261"))
    )
    (comp (ref "X3")
      (value "FPGA DEBUG")
      (footprint "eagle-import:PB-53261-12")
      (libsource (lib "eagle-import") (part "CONN_12-1-53261"))
    )
    (comp (ref "X5")
      (value "CONN_5-2")
      (footprint "eagle-import:FTSH-105-D")
      (libsource (lib "eagle-import") (part "CONN_5-2"))
    )
    (comp (ref "X6")
      (value "CONN_5-1-53261")
      (footprint "eagle-import:PB-53261-05")
      (libsource (lib "eagle-import") (part "CONN_5-1-53261"))
    )
    (comp (ref "C34")
      (value "20pF")
      (footprint "eagle-import:0402-CAP")
      (libsource (lib "eagle-import") (part "CAPACITOR-0402"))
    )
    (comp (ref "C35")
      (value "20pF")
      (footprint "eagle-import:0402-CAP")
      (libsource (lib "eagle-import") (part "CAPACITOR-0402"))
    )
    (comp (ref "C45")
      (value "0.047uF")
      (footprint "eagle-import:C0402")
      (libsource (lib "eagle-import") (part "C-EUC0402"))
    )
    (comp (ref "C49")
      (value "0.047uF")
      (footprint "eagle-import:0402-CAP")
      (libsource (lib "eagle-import") (part "CAPACITOR-0402"))
    )
    (comp (ref "C50")
      (value "4.7uF")
      (footprint "eagle-import:0603-CAP")
      (libsource (lib "eagle-import") (part "CAPACITOR-0603"))
    )
    (comp (ref "C56")
      (value "0.047uF")
      (footprint "eagle-import:0402-CAP")
      (libsource (lib "eagle-import") (part "CAPACITOR-0402"))
    )
    (comp (ref "C57")
      (value "4.7uF")
      (footprint "eagle-import:0603-CAP")
      (libsource (lib "eagle-import") (part "CAPACITOR-0603"))
    )
    (comp (ref "C58")
      (value "0.047uF")
      (footprint "eagle-import:0402-CAP")
      (libsource (lib "eagle-import") (part "CAPACITOR-0402"))
    )
    (comp (ref "C59")
      (value "4.7uF")
      (footprint "eagle-import:0603-CAP")
      (libsource (lib "eagle-import") (part "CAPACITOR-0603"))
    )
    (comp (ref "C64")
      (value "0.047uF")
      (footprint "eagle-import:0402-CAP")
      (libsource (lib "eagle-import") (part "CAPACITOR-0402"))
    )
    (comp (ref "C65")
      (value "4.7uF")
      (footprint "eagle-import:0603-CAP")
      (libsource (lib "eagle-import") (part "CAPACITOR-0603"))
    )
    (comp (ref "C68")
      (value "0.047uF")
      (footprint "eagle-import:0402-CAP")
      (libsource (lib "eagle-import") (part "CAPACITOR-0402"))
    )
    (comp (ref "C69")
      (value "0.047uF")
      (footprint "eagle-import:C0603")
      (libsource (lib "eagle-import") (part "C-EUC0603"))
    )
    (comp (ref "C70")
      (value "0.047uF")
      (footprint "eagle-import:0402-CAP")
      (libsource (lib "eagle-import") (part "CAPACITOR-0402"))
    )
    (comp (ref "C74")
      (value "0.047uF")
      (footprint "eagle-import:0402-CAP")
      (libsource (lib "eagle-import") (part "CAPACITOR-0402"))
    )
    (comp (ref "C75")
      (value "0.047uF")
      (footprint "eagle-import:0402-CAP")
      (libsource (lib "eagle-import") (part "CAPACITOR-0402"))
    )
    (comp (ref "L10")
      (value "Ferrite 600/0.5")
      (footprint "eagle-import:0805-IND")
      (libsource (lib "eagle-import") (part "INDUCTOR-0805"))
    )
    (comp (ref "L11")
      (value "Ferrite 600/0.5")
      (footprint "eagle-import:0805-IND")
      (libsource (lib "eagle-import") (part "INDUCTOR-0805"))
    )
    (comp (ref "R3")
      (value "2K")
      (footprint "eagle-import:0402-RES")
      (libsource (lib "eagle-import") (part "RESISTOR-0402"))
    )
    (comp (ref "R4")
      (value "10k")
      (footprint "eagle-import:0402-RES")
      (libsource (lib "eagle-import") (part "RESISTOR-0402"))
    )
    (comp (ref "R5")
      (value "10k")
      (footprint "eagle-import:0402-RES")
      (libsource (lib "eagle-import") (part "RESISTOR-0402"))
    )
    (comp (ref "R6")
      (value "10k")
      (footprint "eagle-import:0402-RES")
      (libsource (lib "eagle-import") (part "RESISTOR-0402"))
    )
    (comp (ref "R7")
      (value "12k")
      (footprint "eagle-import:0402-RES")
      (libsource (lib "eagle-import") (part "RESISTOR-0402"))
    )
    (comp (ref "R9")
      (value "10k")
      (footprint "eagle-import:0402-RES")
      (libsource (lib "eagle-import") (part "RESISTOR-0402"))
    )
    (comp (ref "U6")
      (value "93LC56BT-I/OT")
      (footprint "eagle-import:93AA56BT-I_OT")
      (libsource (lib "eagle-import") (part "93LC56BT-I/OT"))
    )
    (comp (ref "U7")
      (value "FT232HQ")
      (footprint "eagle-import:FT232HQ")
      (libsource (lib "eagle-import") (part "FT232HQ"))
    )
    (comp (ref "X4")
      (value "NX5032GA-12M")
      (footprint "eagle-import:NX5032GA")
      (libsource (lib "eagle-import") (part "NX5032GA-12M"))
    )
    (comp (ref "C48")
      (value "0.47uF")
      (footprint "eagle-import:0402-CAP")
      (libsource (lib "eagle-import") (part "CAPACITOR-0402"))
    )
    (comp (ref "R13")
      (value "2K")
      (footprint "eagle-import:0402-RES")
      (libsource (lib "eagle-import") (part "RESISTOR-0402"))
    )
    (comp (ref "R14")
      (value "10K")
      (footprint "eagle-import:0402-RES")
      (libsource (lib "eagle-import") (part "RESISTOR-0402"))
    )
    (comp (ref "R15")
      (value "2K")
      (footprint "eagle-import:0402-RES")
      (libsource (lib "eagle-import") (part "RESISTOR-0402"))
    )
    (comp (ref "R16")
      (value "330")
      (footprint "eagle-import:0402-RES")
      (libsource (lib "eagle-import") (part "RESISTOR-0402"))
    )
    (comp (ref "R17")
      (value "2K")
      (footprint "eagle-import:0402-RES")
      (libsource (lib "eagle-import") (part "RESISTOR-0402"))
    )
    (comp (ref "R18")
      (value "2K")
      (footprint "eagle-import:0402-RES")
      (libsource (lib "eagle-import") (part "RESISTOR-0402"))
    )
    (comp (ref "U13")
      (value "M25PX80")
      (footprint "eagle-import:M25P80_MLP8")
      (libsource (lib "eagle-import") (part "M25P80_MLP8"))
    )
    (comp (ref "C1")
      (value "22pF")
      (footprint "eagle-import:0402-CAP")
      (libsource (lib "eagle-import") (part "CAPACITOR-0402"))
    )
    (comp (ref "C2")
      (value "10uF")
      (footprint "eagle-import:1206-CAP")
      (libsource (lib "eagle-import") (part "CAPACITOR-1206"))
    )
    (comp (ref "C3")
      (value "10uF")
      (footprint "eagle-import:1206-CAP")
      (libsource (lib "eagle-import") (part "CAPACITOR-1206"))
    )
    (comp (ref "C4")
      (value "10uF")
      (footprint "eagle-import:1206-CAP")
      (libsource (lib "eagle-import") (part "CAPACITOR-1206"))
    )
    (comp (ref "C5")
      (value "22pF")
      (footprint "eagle-import:0402-CAP")
      (libsource (lib "eagle-import") (part "CAPACITOR-0402"))
    )
    (comp (ref "L13")
      (value "4.7uH")
      (footprint "eagle-import:LQM2HPN4R7MG0L")
      (libsource (lib "eagle-import") (part "LQM2HPN4R7MG0L"))
    )
    (comp (ref "L14")
      (value "4.7uH")
      (footprint "eagle-import:LQM2HPN4R7MG0L")
      (libsource (lib "eagle-import") (part "LQM2HPN4R7MG0L"))
    )
    (comp (ref "Q1")
      (value "IRLML6401")
      (footprint "eagle-import:SOT23-3")
      (libsource (lib "eagle-import") (part "MOSFET-PCHANNELSMD"))
    )
    (comp (ref "R1")
      (value "10K")
      (footprint "eagle-import:0402-RES")
      (libsource (lib "eagle-import") (part "RESISTOR-0402"))
    )
    (comp (ref "R61")
      (value "634K")
      (footprint "eagle-import:0402-RES")
      (libsource (lib "eagle-import") (part "RESISTOR-0402"))
    )
    (comp (ref "R62")
      (value "140K")
      (footprint "eagle-import:0402-RES")
      (libsource (lib "eagle-import") (part "RESISTOR-0402"))
    )
    (comp (ref "R63")
      (value "200k")
      (footprint "eagle-import:0402-RES")
      (libsource (lib "eagle-import") (part "RESISTOR-0402"))
    )
    (comp (ref "R64")
      (value "200k")
      (footprint "eagle-import:0402-RES")
      (libsource (lib "eagle-import") (part "RESISTOR-0402"))
    )
    (comp (ref "U2")
      (value "LTC3407A_DFN")
      (footprint "eagle-import:DFN10")
      (libsource (lib "eagle-import") (part "LTC3407A_DFN"))
    )
  )
  (nets
    (net (code "1") (name "DEBUG0") (class "Default")
      (node (ref "U1") (pin "R1") (pinfunction "IO_L32N_M3DQ15_3_R1") (pintype "bidirectional"))
      (node (ref "X3") (pin "11") (pinfunction "11_11") (pintype "bidirectional"))
    )
    (net (code "2") (name "DEBUG1") (class "Default")
      (node (ref "U1") (pin "N1") (pinfunction "IO_L34N_M3UDQSN_3_N1") (pintype "bidirectional"))
      (node (ref "X3") (pin "10") (pinfunction "10_10") (pintype "bidirectional"))
    )
    (net (code "3") (name "DEBUG2") (class "Default")
      (node (ref "U1") (pin "M1") (pinfunction "IO_L35N_M3DQ11_3_M1") (pintype "bidirectional"))
      (node (ref "X3") (pin "9") (pinfunction "9_9") (pintype "bidirectional"))
    )
    (net (code "4") (name "DEBUG3") (class "Default")
      (node (ref "U1") (pin "L1") (pinfunction "IO_L36N_M3DQ9_3_L1") (pintype "bidirectional"))
      (node (ref "X3") (pin "8") (pinfunction "8_8") (pintype "bidirectional"))
    )
    (net (code "5") (name "DEBUG4") (class "Default")
      (node (ref "U1") (pin "J1") (pinfunction "IO_L38N_M3DQ3_3_J1") (pintype "bidirectional"))
      (node (ref "X3") (pin "7") (pinfunction "7_7") (pintype "bidirectional"))
    )
    (net (code "6") (name "DEBUG5") (class "Default")
      (node (ref "U1") (pin "H3") (pinfunction "IO_L44N_GCLK20_M3A6_3_H3") (pintype "bidirectional"))
      (node (ref "X3") (pin "6") (pinfunction "6_6") (pintype "bidirectional"))
    )
    (net (code "7") (name "DEBUG6") (class "Default")
      (node (ref "U1") (pin "F1") (pinfunction "IO_L41N_GCLK26_M3DQ5_3_F1") (pintype "bidirectional"))
      (node (ref "X3") (pin "5") (pinfunction "5_5") (pintype "bidirectional"))
    )
    (net (code "8") (name "DEBUG7") (class "Default")
      (node (ref "U1") (pin "E1") (pinfunction "IO_L46N_M3CLKN_3_E1") (pintype "bidirectional"))
      (node (ref "X3") (pin "4") (pinfunction "4_4") (pintype "bidirectional"))
    )
    (net (code "9") (name "DEBUG8") (class "Default")
      (node (ref "U1") (pin "D1") (pinfunction "IO_L49N_M3A2_3_D1") (pintype "bidirectional"))
      (node (ref "X3") (pin "3") (pinfunction "3_3") (pintype "bidirectional"))
    )
    (net (code "10") (name "DEBUG9") (class "Default")
      (node (ref "U1") (pin "C1") (pinfunction "IO_L50P_M3WE_3_C1") (pintype "bidirectional"))
      (node (ref "X3") (pin "2") (pinfunction "2_2") (pintype "bidirectional"))
    )
    (net (code "11") (name "FPGA_DONE") (class "Default")
      (node (ref "R16") (pin "P$1") (pinfunction "1_P$1") (pintype "passive"))
      (node (ref "U1") (pin "P13") (pinfunction "DONE_2_P13") (pintype "bidirectional"))
      (node (ref "U3") (pin "9") (pinfunction "PC1-ADC11_9") (pintype "bidirectional"))
    )
    (net (code "12") (name "FPGA_INIT_B") (class "Default")
      (node (ref "R17") (pin "P$2") (pinfunction "2_P$2") (pintype "passive"))
      (node (ref "U1") (pin "R3") (pinfunction "IO_L65P_INIT_B_2_R3") (pintype "bidirectional"))
      (node (ref "U3") (pin "8") (pinfunction "PC0-ADC10_8") (pintype "bidirectional"))
    )
    (net (code "13") (name "FPGA_PROGRAM_B") (class "Default")
      (node (ref "R15") (pin "P$2") (pinfunction "2_P$2") (pintype "passive"))
      (node (ref "U1") (pin "T2") (pinfunction "PROGRAM_B_2_T2") (pintype "input"))
      (node (ref "U3") (pin "53") (pinfunction "PC12--USART3CK_53") (pintype "bidirectional"))
    )
    (net (code "14") (name "FPGA_TDO_STM_TDI") (class "Default")
      (node (ref "U1") (pin "E14") (pinfunction "TDO_E14") (pintype "output"))
      (node (ref "U3") (pin "50") (pinfunction "PA15/JTDI-TIM2CH1ETR/SPI1NSS_50") (pintype "bidirectional"))
    )
    (net (code "15") (name "FTDI_ADBUS2") (class "Default")
      (node (ref "U1") (pin "T15") (pinfunction "IO_L50N_M1UDQSN_1_T15") (pintype "bidirectional"))
      (node (ref "U7") (pin "15") (pinfunction "AD2_15") (pintype "bidirectional"))
    )
    (net (code "16") (name "FTDI_ADBUS3") (class "Default")
      (node (ref "U1") (pin "R15") (pinfunction "IO_L49P_M1DQ10_1_R15") (pintype "bidirectional"))
      (node (ref "U7") (pin "16") (pinfunction "AD3_16") (pintype "bidirectional"))
    )
    (net (code "17") (name "FTDI_ADBUS4") (class "Default")
      (node (ref "U1") (pin "P16") (pinfunction "IO_L48N_M1DQ9_1_P16") (pintype "bidirectional"))
      (node (ref "U7") (pin "17") (pinfunction "AD4_17") (pintype "bidirectional"))
    )
    (net (code "18") (name "FTDI_ADBUS5") (class "Default")
      (node (ref "U1") (pin "N14") (pinfunction "IO_L45P_A1_M1LDQS_1_N14") (pintype "bidirectional"))
      (node (ref "U7") (pin "18") (pinfunction "AD5_18") (pintype "bidirectional"))
    )
    (net (code "19") (name "FTDI_ADBUS6") (class "Default")
      (node (ref "U1") (pin "N16") (pinfunction "IO_L45N_A0_M1LDQSN_1_N16") (pintype "bidirectional"))
      (node (ref "U7") (pin "19") (pinfunction "AD6_19") (pintype "bidirectional"))
    )
    (net (code "20") (name "FTDI_ADBUS7") (class "Default")
      (node (ref "U1") (pin "M14") (pinfunction "IO_L74N_DOUT_BUSY_1_M14") (pintype "bidirectional"))
      (node (ref "U7") (pin "20") (pinfunction "AD7_20") (pintype "bidirectional"))
    )
    (net (code "21") (name "FTDI_CLKOUT") (class "Default")
      (node (ref "U1") (pin "K14") (pinfunction "IO_L41N_GCLK8_M1CASN_1_K14") (pintype "bidirectional"))
      (node (ref "U7") (pin "29") (pinfunction "AC5_29") (pintype "bidirectional"))
    )
    (net (code "22") (name "FTDI_NOE") (class "Default")
      (node (ref "U1") (pin "K16") (pinfunction "IO_L44N_A2_M1DQ7_1_K16") (pintype "bidirectional"))
      (node (ref "U7") (pin "30") (pinfunction "AC6_30") (pintype "bidirectional"))
    )
    (net (code "23") (name "FTDI_NRD") (class "Default")
      (node (ref "U1") (pin "L14") (pinfunction "IO_L47P_FWE_B_M1DQ0_1_L14") (pintype "bidirectional"))
      (node (ref "U7") (pin "26") (pinfunction "AC2_26") (pintype "bidirectional"))
    )
    (net (code "24") (name "FTDI_NRST") (class "Default")
      (node (ref "U3") (pin "27") (pinfunction "PB1-ADC9/TIM3CH4-TIM1CH3N_27") (pintype "bidirectional"))
      (node (ref "U7") (pin "34") (pinfunction "NRESET_34") (pintype "input"))
    )
    (net (code "25") (name "FTDI_NRXF") (class "Default")
      (node (ref "U1") (pin "M15") (pinfunction "IO_L46P_FCS_B_M1DQ2_1_M15") (pintype "bidirectional"))
      (node (ref "U7") (pin "21") (pinfunction "AC0_21") (pintype "bidirectional"))
    )
    (net (code "26") (name "FTDI_NSIWU") (class "Default")
      (node (ref "U1") (pin "K15") (pinfunction "IO_L44P_A3_M1DQ6_1_K15") (pintype "bidirectional"))
      (node (ref "U7") (pin "28") (pinfunction "AC4_28") (pintype "bidirectional"))
    )
    (net (code "27") (name "FTDI_NTXE") (class "Default")
      (node (ref "U1") (pin "M16") (pinfunction "IO_L46N_FOE_B_M1DQ3_1_M16") (pintype "bidirectional"))
      (node (ref "U7") (pin "25") (pinfunction "AC1_25") (pintype "bidirectional"))
    )
    (net (code "28") (name "FTDI_NWR") (class "Default")
      (node (ref "U1") (pin "L16") (pinfunction "IO_L47N_LDC_M1DQ1_1_L16") (pintype "bidirectional"))
      (node (ref "U7") (pin "27") (pinfunction "AC3_27") (pintype "bidirectional"))
    )
    (net (code "29") (name "GND") (class "Default")
      (node (ref "B1") (pin "P$2") (pinfunction "2_P$2") (pintype "bidirectional"))
      (node (ref "C10") (pin "P$2") (pinfunction "2_P$2") (pintype "passive"))
      (node (ref "C107") (pin "P$2") (pinfunction "2_P$2") (pintype "passive"))
      (node (ref "C11") (pin "P$1") (pinfunction "1_P$1") (pintype "passive"))
      (node (ref "C12") (pin "P$1") (pinfunction "1_P$1") (pintype "passive"))
      (node (ref "C13") (pin "P$1") (pinfunction "1_P$1") (pintype "passive"))
      (node (ref "C15") (pin "P$1") (pinfunction "1_P$1") (pintype "passive"))
      (node (ref "C17") (pin "P$2") (pinfunction "2_P$2") (pintype "passive"))
      (node (ref "C18") (pin "P$2") (pinfunction "2_P$2") (pintype "passive"))
      (node (ref "C19") (pin "P$2") (pinfunction "2_P$2") (pintype "passive"))
      (node (ref "C2") (pin "P$2") (pinfunction "2_P$2") (pintype "passive"))
      (node (ref "C21") (pin "P$2") (pinfunction "2_P$2") (pintype "bidirectional"))
      (node (ref "C22") (pin "P$2") (pinfunction "2_P$2") (pintype "passive"))
      (node (ref "C23") (pin "P$2") (pinfunction "2_P$2") (pintype "passive"))
      (node (ref "C24") (pin "P$2") (pinfunction "2_P$2") (pintype "bidirectional"))
      (node (ref "C25") (pin "P$2") (pinfunction "2_P$2") (pintype "bidirectional"))
      (node (ref "C26") (pin "P$2") (pinfunction "2_P$2") (pintype "bidirectional"))
      (node (ref "C27") (pin "P$2") (pinfunction "2_P$2") (pintype "passive"))
      (node (ref "C28") (pin "P$2") (pinfunction "2_P$2") (pintype "passive"))
      (node (ref "C29") (pin "P$2") (pinfunction "2_P$2") (pintype "passive"))
      (node (ref "C3") (pin "P$2") (pinfunction "2_P$2") (pintype "passive"))
      (node (ref "C30") (pin "P$2") (pinfunction "2_P$2") (pintype "passive"))
      (node (ref "C31") (pin "P$2") (pinfunction "2_P$2") (pintype "passive"))
      (node (ref "C32") (pin "P$2") (pinfunction "2_P$2") (pintype "passive"))
      (node (ref "C33") (pin "P$1") (pinfunction "1_P$1") (pintype "passive"))
      (node (ref "C34") (pin "P$2") (pinfunction "2_P$2") (pintype "passive"))
      (node (ref "C35") (pin "P$2") (pinfunction "2_P$2") (pintype "passive"))
      (node (ref "C36") (pin "P$1") (pinfunction "1_P$1") (pintype "passive"))
      (node (ref "C37") (pin "P$2") (pinfunction "2_P$2") (pintype "passive"))
      (node (ref "C38") (pin "P$2") (pinfunction "2_P$2") (pintype "passive"))
      (node (ref "C39") (pin "P$2") (pinfunction "2_P$2") (pintype "passive"))
      (node (ref "C4") (pin "P$2") (pinfunction "2_P$2") (pintype "passive"))
      (node (ref "C40") (pin "P$2") (pinfunction "2_P$2") (pintype "passive"))
      (node (ref "C41") (pin "P$1") (pinfunction "1_P$1") (pintype "passive"))
      (node (ref "C42") (pin "P$2") (pinfunction "2_P$2") (pintype "passive"))
      (node (ref "C43") (pin "P$2") (pinfunction "2_P$2") (pintype "passive"))
      (node (ref "C44") (pin "P$2") (pinfunction "2_P$2") (pintype "passive"))
      (node (ref "C45") (pin "2") (pinfunction "2_2") (pintype "passive"))
      (node (ref "C46") (pin "P$2") (pinfunction "2_P$2") (pintype "passive"))
      (node (ref "C47") (pin "P$1") (pinfunction "1_P$1") (pintype "passive"))
      (node (ref "C48") (pin "P$2") (pinfunction "2_P$2") (pintype "passive"))
      (node (ref "C49") (pin "P$2") (pinfunction "2_P$2") (pintype "passive"))
      (node (ref "C50") (pin "P$1") (pinfunction "1_P$1") (pintype "passive"))
      (node (ref "C51") (pin "P$1") (pinfunction "1_P$1") (pintype "passive"))
      (node (ref "C52") (pin "P$2") (pinfunction "2_P$2") (pintype "passive"))
      (node (ref "C53") (pin "P$2") (pinfunction "2_P$2") (pintype "passive"))
      (node (ref "C54") (pin "P$2") (pinfunction "2_P$2") (pintype "passive"))
      (node (ref "C55") (pin "P$2") (pinfunction "2_P$2") (pintype "passive"))
      (node (ref "C56") (pin "P$2") (pinfunction "2_P$2") (pintype "passive"))
      (node (ref "C57") (pin "P$1") (pinfunction "1_P$1") (pintype "passive"))
      (node (ref "C58") (pin "P$2") (pinfunction "2_P$2") (pintype "passive"))
      (node (ref "C59") (pin "P$1") (pinfunction "1_P$1") (pintype "passive"))
      (node (ref "C6") (pin "P$1") (pinfunction "1_P$1") (pintype "passive"))
      (node (ref "C60") (pin "P$2") (pinfunction "2_P$2") (pintype "passive"))
      (node (ref "C61") (pin "P$2") (pinfunction "2_P$2") (pintype "passive"))
      (node (ref "C62") (pin "P$2") (pinfunction "2_P$2") (pintype "passive"))
      (node (ref "C63") (pin "P$2") (pinfunction "2_P$2") (pintype "passive"))
      (node (ref "C64") (pin "P$2") (pinfunction "2_P$2") (pintype "passive"))
      (node (ref "C65") (pin "P$1") (pinfunction "1_P$1") (pintype "passive"))
      (node (ref "C66") (pin "P$2") (pinfunction "2_P$2") (pintype "passive"))
      (node (ref "C67") (pin "P$2") (pinfunction "2_P$2") (pintype "passive"))
      (node (ref "C68") (pin "P$2") (pinfunction "2_P$2") (pintype "passive"))
      (node (ref "C69") (pin "2") (pinfunction "2_2") (pintype "passive"))
      (node (ref "C7") (pin "P$1") (pinfunction "1_P$1") (pintype "passive"))
      (node (ref "C70") (pin "P$2") (pinfunction "2_P$2") (pintype "passive"))
      (node (ref "C71") (pin "P$2") (pinfunction "2_P$2") (pintype "passive"))
      (node (ref "C72") (pin "P$2") (pinfunction "2_P$2") (pintype "passive"))
      (node (ref "C73") (pin "P$2") (pinfunction "2_P$2") (pintype "passive"))
      (node (ref "C74") (pin "P$2") (pinfunction "2_P$2") (pintype "passive"))
      (node (ref "C75") (pin "P$2") (pinfunction "2_P$2") (pintype "passive"))
      (node (ref "C76") (pin "P$2") (pinfunction "2_P$2") (pintype "passive"))
      (node (ref "C77") (pin "P$2") (pinfunction "2_P$2") (pintype "passive"))
      (node (ref "C78") (pin "P$2") (pinfunction "2_P$2") (pintype "passive"))
      (node (ref "C8") (pin "P$2") (pinfunction "2_P$2") (pintype "passive"))
      (node (ref "C80") (pin "P$2") (pinfunction "2_P$2") (pintype "passive"))
      (node (ref "C81") (pin "P$2") (pinfunction "2_P$2") (pintype "passive"))
      (node (ref "C82") (pin "P$1") (pinfunction "1_P$1") (pintype "passive"))
      (node (ref "C86") (pin "P$2") (pinfunction "2_P$2") (pintype "bidirectional"))
      (node (ref "C87") (pin "P$2") (pinfunction "2_P$2") (pintype "bidirectional"))
      (node (ref "C9") (pin "P$2") (pinfunction "2_P$2") (pintype "passive"))
      (node (ref "C96") (pin "P$2") (pinfunction "2_P$2") (pintype "passive"))
      (node (ref "H2") (pin "B3,0") (pinfunction "MOUNT_B3,0") (pintype "passive"))
      (node (ref "H3") (pin "B3,0") (pinfunction "MOUNT_B3,0") (pintype "passive"))
      (node (ref "H4") (pin "B3,0") (pinfunction "MOUNT_B3,0") (pintype "passive"))
      (node (ref "H5") (pin "B3,0") (pinfunction "MOUNT_B3,0") (pintype "passive"))
      (node (ref "J1") (pin "P2") (pinfunction "2_P2") (pintype "power_in"))
      (node (ref "J1") (pin "P3") (pinfunction "3_P3") (pintype "power_in"))
      (node (ref "J1") (pin "P4") (pinfunction "4_P4") (pintype "power_in"))
      (node (ref "J1") (pin "P5") (pinfunction "5_P5") (pintype "power_in"))
      (node (ref "J6") (pin "PIN_5") (pinfunction "5_PIN_5") (pintype "input"))
      (node (ref "L5") (pin "P$1") (pinfunction "1_P$1") (pintype "passive"))
      (node (ref "Q1") (pin "1") (pinfunction "G_1") (pintype "passive"))
      (node (ref "R14") (pin "P$2") (pinfunction "2_P$2") (pintype "passive"))
      (node (ref "R18") (pin "P$1") (pinfunction "1_P$1") (pintype "passive"))
      (node (ref "R20") (pin "P$1") (pinfunction "1_P$1") (pintype "passive"))
      (node (ref "R62") (pin "P$2") (pinfunction "2_P$2") (pintype "passive"))
      (node (ref "R63") (pin "P$2") (pinfunction "2_P$2") (pintype "passive"))
      (node (ref "R7") (pin "P$2") (pinfunction "2_P$2") (pintype "passive"))
      (node (ref "R8") (pin "P$1") (pinfunction "1_P$1") (pintype "passive"))
      (node (ref "SHLD2") (pin "1") (pinfunction "P$1_1") (pintype "power_in"))
      (node (ref "SHLD2") (pin "10") (pinfunction "P$10_10") (pintype "power_in"))
      (node (ref "SHLD2") (pin "11") (pinfunction "P$11_11") (pintype "power_in"))
      (node (ref "SHLD2") (pin "12") (pinfunction "P$12_12") (pintype "power_in"))
      (node (ref "SHLD2") (pin "13") (pinfunction "P$13_13") (pintype "power_in"))
      (node (ref "SHLD2") (pin "14") (pinfunction "P$14_14") (pintype "power_in"))
      (node (ref "SHLD2") (pin "15") (pinfunction "P$15_15") (pintype "power_in"))
      (node (ref "SHLD2") (pin "16") (pinfunction "P$16_16") (pintype "power_in"))
      (node (ref "SHLD2") (pin "17") (pinfunction "P$17_17") (pintype "power_in"))
      (node (ref "SHLD2") (pin "18") (pinfunction "P$18_18") (pintype "power_in"))
      (node (ref "SHLD2") (pin "19") (pinfunction "P$19_19") (pintype "power_in"))
      (node (ref "SHLD2") (pin "2") (pinfunction "P$2_2") (pintype "power_in"))
      (node (ref "SHLD2") (pin "20") (pinfunction "P$20_20") (pintype "power_in"))
      (node (ref "SHLD2") (pin "21") (pinfunction "P$21_21") (pintype "power_in"))
      (node (ref "SHLD2") (pin "22") (pinfunction "P$22_22") (pintype "power_in"))
      (node (ref "SHLD2") (pin "23") (pinfunction "P$23_23") (pintype "power_in"))
      (node (ref "SHLD2") (pin "24") (pinfunction "P$24_24") (pintype "power_in"))
      (node (ref "SHLD2") (pin "25") (pinfunction "P$25_25") (pintype "power_in"))
      (node (ref "SHLD2") (pin "26") (pinfunction "P$26_26") (pintype "power_in"))
      (node (ref "SHLD2") (pin "27") (pinfunction "P$27_27") (pintype "power_in"))
      (node (ref "SHLD2") (pin "28") (pinfunction "P$28_28") (pintype "power_in"))
      (node (ref "SHLD2") (pin "3") (pinfunction "P$3_3") (pintype "power_in"))
      (node (ref "SHLD2") (pin "4") (pinfunction "P$4_4") (pintype "power_in"))
      (node (ref "SHLD2") (pin "5") (pinfunction "P$5_5") (pintype "power_in"))
      (node (ref "SHLD2") (pin "6") (pinfunction "P$6_6") (pintype "power_in"))
      (node (ref "SHLD2") (pin "7") (pinfunction "P$7_7") (pintype "power_in"))
      (node (ref "SHLD2") (pin "8") (pinfunction "P$8_8") (pintype "power_in"))
      (node (ref "SHLD2") (pin "9") (pinfunction "P$9_9") (pintype "power_in"))
      (node (ref "U1") (pin "A1") (pinfunction "GND_A1") (pintype "power_in"))
      (node (ref "U1") (pin "A16") (pinfunction "GND_A16") (pintype "power_in"))
      (node (ref "U1") (pin "B11") (pinfunction "GND_B11") (pintype "power_in"))
      (node (ref "U1") (pin "B7") (pinfunction "GND_B7") (pintype "power_in"))
      (node (ref "U1") (pin "D13") (pinfunction "GND_D13") (pintype "power_in"))
      (node (ref "U1") (pin "D4") (pinfunction "GND_D4") (pintype "power_in"))
      (node (ref "U1") (pin "E9") (pinfunction "GND_E9") (pintype "power_in"))
      (node (ref "U1") (pin "G15") (pinfunction "GND_G15") (pintype "power_in"))
      (node (ref "U1") (pin "G2") (pinfunction "GND_G2") (pintype "power_in"))
      (node (ref "U1") (pin "G8") (pinfunction "GND_G8") (pintype "power_in"))
      (node (ref "U1") (pin "H12") (pinfunction "GND_H12") (pintype "power_in"))
      (node (ref "U1") (pin "H7") (pinfunction "GND_H7") (pintype "power_in"))
      (node (ref "U1") (pin "H9") (pinfunction "GND_H9") (pintype "power_in"))
      (node (ref "U1") (pin "J5") (pinfunction "GND_J5") (pintype "power_in"))
      (node (ref "U1") (pin "J8") (pinfunction "GND_J8") (pintype "power_in"))
      (node (ref "U1") (pin "K7") (pinfunction "GND_K7") (pintype "power_in"))
      (node (ref "U1") (pin "K9") (pinfunction "GND_K9") (pintype "power_in"))
      (node (ref "U1") (pin "L15") (pinfunction "GND_L15") (pintype "power_in"))
      (node (ref "U1") (pin "L2") (pinfunction "GND_L2") (pintype "power_in"))
      (node (ref "U1") (pin "M8") (pinfunction "GND_M8") (pintype "power_in"))
      (node (ref "U1") (pin "N11") (pinfunction "IO_L13P_M1_2_N11") (pintype "bidirectional"))
      (node (ref "U1") (pin "N13") (pinfunction "GND_N13") (pintype "power_in"))
      (node (ref "U1") (pin "P3") (pinfunction "GND_P3") (pintype "power_in"))
      (node (ref "U1") (pin "R10") (pinfunction "GND_R10") (pintype "power_in"))
      (node (ref "U1") (pin "R6") (pinfunction "GND_R6") (pintype "power_in"))
      (node (ref "U1") (pin "T1") (pinfunction "GND_T1") (pintype "power_in"))
      (node (ref "U1") (pin "T16") (pinfunction "GND_T16") (pintype "power_in"))
      (node (ref "U10") (pin "29") (pinfunction "EPGND_29") (pintype "bidirectional"))
      (node (ref "U12") (pin "2") (pinfunction "GND_2") (pintype "bidirectional"))
      (node (ref "U13") (pin "4") (pinfunction "GND_4") (pintype "power_in"))
      (node (ref "U13") (pin "9") (pinfunction "EP_9") (pintype "power_in"))
      (node (ref "U2") (pin "11") (pinfunction "GND2_11") (pintype "bidirectional"))
      (node (ref "U2") (pin "5") (pinfunction "GND1_5") (pintype "bidirectional"))
      (node (ref "U3") (pin "12") (pinfunction "VSSA_12") (pintype "power_in"))
      (node (ref "U3") (pin "18") (pinfunction "VSS4_18") (pintype "bidirectional"))
      (node (ref "U3") (pin "60") (pinfunction "BOOT0_60") (pintype "input"))
      (node (ref "U3") (pin "63") (pinfunction "VSS3_63") (pintype "power_in"))
      (node (ref "U4") (pin "1") (pinfunction "GND1_1") (pintype "bidirectional"))
      (node (ref "U4") (pin "2") (pinfunction "GND2_2") (pintype "bidirectional"))
      (node (ref "U5") (pin "2") (pinfunction "2_2") (pintype "power_in"))
      (node (ref "U5") (pin "3") (pinfunction "3_3") (pintype "power_in"))
      (node (ref "U5") (pin "4") (pinfunction "4_4") (pintype "power_in"))
      (node (ref "U5") (pin "5") (pinfunction "5_5") (pintype "power_in"))
      (node (ref "U6") (pin "2") (pinfunction "VSS_2") (pintype "power_in"))
      (node (ref "U7") (pin "10") (pinfunction "GND1_10") (pintype "power_in"))
      (node (ref "U7") (pin "11") (pinfunction "GND2_11") (pintype "power_in"))
      (node (ref "U7") (pin "22") (pinfunction "GND3_22") (pintype "power_in"))
      (node (ref "U7") (pin "23") (pinfunction "GND4_23") (pintype "power_in"))
      (node (ref "U7") (pin "35") (pinfunction "GND5_35") (pintype "power_in"))
      (node (ref "U7") (pin "36") (pinfunction "GND6_36") (pintype "power_in"))
      (node (ref "U7") (pin "4") (pinfunction "AGND1_4") (pintype "power_in"))
      (node (ref "U7") (pin "41") (pinfunction "AGND3_41") (pintype "power_in"))
      (node (ref "U7") (pin "42") (pinfunction "TEST_42") (pintype "input"))
      (node (ref "U7") (pin "47") (pinfunction "GND7_47") (pintype "power_in"))
      (node (ref "U7") (pin "48") (pinfunction "GND8_48") (pintype "power_in"))
      (node (ref "U7") (pin "49") (pinfunction "EPGND_49") (pintype "power_in"))
      (node (ref "U7") (pin "9") (pinfunction "AGND2_9") (pintype "power_in"))
      (node (ref "U8") (pin "2") (pinfunction "GND1_2") (pintype "power_in"))
      (node (ref "U8") (pin "3") (pinfunction "GND2_3") (pintype "power_in"))
      (node (ref "U8") (pin "5") (pinfunction "GND3_5") (pintype "power_in"))
      (node (ref "U9") (pin "3") (pinfunction "VSS_3") (pintype "bidirectional"))
      (node (ref "X1") (pin "1") (pinfunction "1_1") (pintype "bidirectional"))
      (node (ref "X3") (pin "1") (pinfunction "1_1") (pintype "bidirectional"))
      (node (ref "X5") (pin "3") (pinfunction "3_3") (pintype "bidirectional"))
      (node (ref "X5") (pin "5") (pinfunction "5_5") (pintype "bidirectional"))
      (node (ref "X5") (pin "7") (pinfunction "7_7") (pintype "bidirectional"))
      (node (ref "X5") (pin "9") (pinfunction "9_9") (pintype "bidirectional"))
      (node (ref "X6") (pin "1") (pinfunction "1_1") (pintype "bidirectional"))
    )
    (net (code "30") (name "JTAG_RST") (class "Default")
      (node (ref "B1") (pin "P$1") (pinfunction "1_P$1") (pintype "bidirectional"))
      (node (ref "C32") (pin "P$1") (pinfunction "1_P$1") (pintype "passive"))
      (node (ref "R34") (pin "P$1") (pinfunction "1_P$1") (pintype "passive"))
      (node (ref "U3") (pin "7") (pinfunction "NRST_7") (pintype "bidirectional"))
      (node (ref "X5") (pin "10") (pinfunction "10_10") (pintype "bidirectional"))
    )
    (net (code "31") (name "JTAG_TCK") (class "Default")
      (node (ref "U1") (pin "C14") (pinfunction "TCK_C14") (pintype "input"))
      (node (ref "U3") (pin "49") (pinfunction "PA14/JTCK/SWCLK_49") (pintype "bidirectional"))
      (node (ref "X5") (pin "4") (pinfunction "4_4") (pintype "bidirectional"))
    )
    (net (code "32") (name "JTAG_TDI") (class "Default")
      (node (ref "U1") (pin "C12") (pinfunction "TDI_C12") (pintype "input"))
      (node (ref "X5") (pin "8") (pinfunction "8_8") (pintype "bidirectional"))
    )
    (net (code "33") (name "JTAG_TDO") (class "Default")
      (node (ref "U3") (pin "55") (pinfunction "PB3/JTDO--TIM2CH2/TRACESWO/SPI1SCK_55") (pintype "bidirectional"))
      (node (ref "X5") (pin "6") (pinfunction "6_6") (pintype "bidirectional"))
    )
    (net (code "34") (name "JTAG_TMS") (class "Default")
      (node (ref "U1") (pin "A15") (pinfunction "TMS_A15") (pintype "input"))
      (node (ref "U3") (pin "46") (pinfunction "PA13/JTMS/SWDIO_46") (pintype "bidirectional"))
      (node (ref "X5") (pin "2") (pinfunction "2_2") (pintype "bidirectional"))
    )
    (net (code "35") (name "MAX_ANT_FLAG") (class "Default")
      (node (ref "U10") (pin "1") (pinfunction "ANT_FLAG_1") (pintype "bidirectional"))
      (node (ref "U3") (pin "25") (pinfunction "PC5-ADC15_25") (pintype "bidirectional"))
    )
    (net (code "36") (name "MAX_CLKOUT") (class "Default")
      (node (ref "U1") (pin "J14") (pinfunction "IO_L43P_GCLK5_M1DQ4_1_J14") (pintype "bidirectional"))
      (node (ref "U10") (pin "16") (pinfunction "CLK_OUT_16") (pintype "bidirectional"))
    )
    (net (code "37") (name "MAX_I0") (class "Default")
      (node (ref "U1") (pin "E16") (pinfunction "IO_L34N_A12_M1BA2_1_E16") (pintype "bidirectional"))
      (node (ref "U10") (pin "20") (pinfunction "I0_20") (pintype "bidirectional"))
    )
    (net (code "38") (name "MAX_I1") (class "Default")
      (node (ref "U1") (pin "E15") (pinfunction "IO_L34P_A13_M1WE_1_E15") (pintype "bidirectional"))
      (node (ref "U10") (pin "21") (pinfunction "I1_21") (pintype "bidirectional"))
    )
    (net (code "39") (name "MAX_LD") (class "Default")
      (node (ref "U10") (pin "6") (pinfunction "LD_6") (pintype "bidirectional"))
      (node (ref "U3") (pin "41") (pinfunction "PA8-USART1CK/MCO/TIM1CH1_41") (pintype "bidirectional"))
    )
    (net (code "40") (name "MAX_NIDLE") (class "Default")
      (node (ref "R12") (pin "P$1") (pinfunction "1_P$1") (pintype "passive"))
      (node (ref "U10") (pin "24") (pinfunction "~{IDLE}_24") (pintype "bidirectional"))
      (node (ref "U3") (pin "29") (pinfunction "PB10-I2C2SCL/USART3TX-TIM2CH3_29") (pintype "bidirectional"))
    )
    (net (code "41") (name "MAX_NSHDN") (class "Default")
      (node (ref "R19") (pin "P$1") (pinfunction "1_P$1") (pintype "passive"))
      (node (ref "U10") (pin "7") (pinfunction "~{SHDN}_7") (pintype "bidirectional"))
      (node (ref "U3") (pin "62") (pinfunction "PB9-TIM4CH4-I2C1SDA/CANTX_62") (pintype "bidirectional"))
    )
    (net (code "42") (name "MAX_PGM") (class "Default")
      (node (ref "R20") (pin "P$2") (pinfunction "2_P$2") (pintype "passive"))
      (node (ref "U10") (pin "26") (pinfunction "PGM_26") (pintype "bidirectional"))
      (node (ref "U3") (pin "61") (pinfunction "PB8-TIM4CH3-I2C1SCL/CANRX_61") (pintype "bidirectional"))
    )
    (net (code "43") (name "MAX_Q0") (class "Default")
      (node (ref "U1") (pin "F15") (pinfunction "IO_L35P_A11_M1A7_1_F15") (pintype "bidirectional"))
      (node (ref "U10") (pin "18") (pinfunction "Q0_18") (pintype "bidirectional"))
    )
    (net (code "44") (name "MAX_Q1") (class "Default")
      (node (ref "U1") (pin "F16") (pinfunction "IO_L35N_A10_M1A2_1_F16") (pintype "bidirectional"))
      (node (ref "U10") (pin "17") (pinfunction "Q1_17") (pintype "bidirectional"))
    )
    (net (code "45") (name "Net-(C1-1)") (class "Default")
      (node (ref "C1") (pin "P$1") (pinfunction "1_P$1") (pintype "passive"))
      (node (ref "R61") (pin "P$1") (pinfunction "1_P$1") (pintype "passive"))
      (node (ref "R62") (pin "P$1") (pinfunction "1_P$1") (pintype "passive"))
      (node (ref "U2") (pin "1") (pinfunction "VFB1_1") (pintype "bidirectional"))
    )
    (net (code "46") (name "Net-(C5-2)") (class "Default")
      (node (ref "C5") (pin "P$2") (pinfunction "2_P$2") (pintype "passive"))
      (node (ref "R63") (pin "P$1") (pinfunction "1_P$1") (pintype "passive"))
      (node (ref "R64") (pin "P$1") (pinfunction "1_P$1") (pintype "passive"))
      (node (ref "U2") (pin "10") (pinfunction "VFB2_10") (pintype "bidirectional"))
    )
    (net (code "47") (name "Net-(C7-2)") (class "Default")
      (node (ref "C7") (pin "P$2") (pinfunction "2_P$2") (pintype "passive"))
      (node (ref "C9") (pin "P$1") (pinfunction "1_P$1") (pintype "passive"))
      (node (ref "R65") (pin "P$2") (pinfunction "2_P$2") (pintype "passive"))
      (node (ref "U12") (pin "1") (pinfunction "VIN_1") (pintype "bidirectional"))
      (node (ref "U12") (pin "3") (pinfunction "EN_3") (pintype "bidirectional"))
    )
    (net (code "48") (name "Net-(C12-2)") (class "Default")
      (node (ref "C12") (pin "P$2") (pinfunction "2_P$2") (pintype "passive"))
      (node (ref "C13") (pin "P$2") (pinfunction "2_P$2") (pintype "passive"))
      (node (ref "C36") (pin "P$2") (pinfunction "2_P$2") (pintype "passive"))
      (node (ref "C41") (pin "P$2") (pinfunction "2_P$2") (pintype "passive"))
      (node (ref "L1") (pin "P$1") (pinfunction "1_P$1") (pintype "passive"))
      (node (ref "L3") (pin "P$2") (pinfunction "2_P$2") (pintype "passive"))
      (node (ref "U10") (pin "3") (pinfunction "ANT_BIAS_3") (pintype "bidirectional"))
    )
    (net (code "49") (name "Net-(C14-1)") (class "Default")
      (node (ref "C14") (pin "P$1") (pinfunction "1_P$1") (pintype "passive"))
      (node (ref "J1") (pin "P1") (pinfunction "1_P1") (pintype "bidirectional"))
      (node (ref "L3") (pin "P$1") (pinfunction "1_P$1") (pintype "passive"))
    )
    (net (code "50") (name "Net-(C14-2)") (class "Default")
      (node (ref "C14") (pin "P$2") (pinfunction "2_P$2") (pintype "passive"))
      (node (ref "U10") (pin "25") (pinfunction "LNA_IN2_25") (pintype "bidirectional"))
    )
    (net (code "51") (name "Net-(C15-2)") (class "Default")
      (node (ref "C15") (pin "P$2") (pinfunction "2_P$2") (pintype "passive"))
      (node (ref "C47") (pin "P$2") (pinfunction "2_P$2") (pintype "passive"))
      (node (ref "R11") (pin "P$1") (pinfunction "1_P$1") (pintype "passive"))
      (node (ref "U9") (pin "1") (pinfunction "VDD_1") (pintype "bidirectional"))
    )
    (net (code "52") (name "Net-(C16-1)") (class "Default")
      (node (ref "C16") (pin "P$1") (pinfunction "1_P$1") (pintype "passive"))
      (node (ref "L1") (pin "P$2") (pinfunction "2_P$2") (pintype "passive"))
      (node (ref "U5") (pin "1") (pinfunction "1_1") (pintype "bidirectional"))
    )
    (net (code "53") (name "Net-(C16-2)") (class "Default")
      (node (ref "C16") (pin "P$2") (pinfunction "2_P$2") (pintype "passive"))
      (node (ref "L4") (pin "P$1") (pinfunction "1_P$1") (pintype "passive"))
      (node (ref "L5") (pin "P$2") (pinfunction "2_P$2") (pintype "passive"))
    )
    (net (code "54") (name "Net-(C18-1)") (class "Default")
      (node (ref "C18") (pin "P$1") (pinfunction "1_P$1") (pintype "passive"))
      (node (ref "R2") (pin "P$1") (pinfunction "1_P$1") (pintype "passive"))
    )
    (net (code "55") (name "Net-(C19-1)") (class "Default")
      (node (ref "C19") (pin "P$1") (pinfunction "1_P$1") (pintype "passive"))
      (node (ref "R2") (pin "P$2") (pinfunction "2_P$2") (pintype "passive"))
      (node (ref "U10") (pin "12") (pinfunction "CP_OUT_12") (pintype "bidirectional"))
    )
    (net (code "56") (name "Net-(C20-1)") (class "Default")
      (node (ref "C20") (pin "P$1") (pinfunction "1_P$1") (pintype "passive"))
      (node (ref "U10") (pin "15") (pinfunction "XTAL_15") (pintype "bidirectional"))
    )
    (net (code "57") (name "Net-(C20-2)") (class "Default")
      (node (ref "C20") (pin "P$2") (pinfunction "2_P$2") (pintype "passive"))
      (node (ref "U4") (pin "3") (pinfunction "OUT_3") (pintype "bidirectional"))
    )
    (net (code "58") (name "Net-(C34-1)") (class "Default")
      (node (ref "C34") (pin "P$1") (pinfunction "1_P$1") (pintype "passive"))
      (node (ref "U7") (pin "2") (pinfunction "XCSO_2") (pintype "output"))
      (node (ref "X4") (pin "2") (pinfunction "2_2") (pintype "bidirectional"))
    )
    (net (code "59") (name "Net-(C35-1)") (class "Default")
      (node (ref "C35") (pin "P$1") (pinfunction "1_P$1") (pintype "passive"))
      (node (ref "U7") (pin "1") (pinfunction "XCSI_1") (pintype "input"))
      (node (ref "X4") (pin "1") (pinfunction "1_1") (pintype "bidirectional"))
    )
    (net (code "60") (name "Net-(C38-1)") (class "Default")
      (node (ref "C38") (pin "P$1") (pinfunction "1_P$1") (pintype "passive"))
      (node (ref "L2") (pin "P$1") (pinfunction "1_P$1") (pintype "passive"))
      (node (ref "U10") (pin "4") (pinfunction "VCCRF_4") (pintype "bidirectional"))
    )
    (net (code "61") (name "Net-(C49-1)") (class "Default")
      (node (ref "C49") (pin "P$1") (pinfunction "1_P$1") (pintype "passive"))
      (node (ref "U7") (pin "38") (pinfunction "VCCCORE_38") (pintype "output"))
    )
    (net (code "62") (name "Net-(C59-2)") (class "Default")
      (node (ref "C59") (pin "P$2") (pinfunction "2_P$2") (pintype "passive"))
      (node (ref "C64") (pin "P$1") (pinfunction "1_P$1") (pintype "passive"))
      (node (ref "L10") (pin "P$2") (pinfunction "2_P$2") (pintype "passive"))
      (node (ref "U7") (pin "3") (pinfunction "VPHY_3") (pintype "power_in"))
    )
    (net (code "63") (name "Net-(C65-2)") (class "Default")
      (node (ref "C65") (pin "P$2") (pinfunction "2_P$2") (pintype "passive"))
      (node (ref "C68") (pin "P$1") (pinfunction "1_P$1") (pintype "passive"))
      (node (ref "L11") (pin "P$2") (pinfunction "2_P$2") (pintype "passive"))
      (node (ref "U7") (pin "8") (pinfunction "VPLL_8") (pintype "power_in"))
    )
    (net (code "64") (name "Net-(C66-1)") (class "Default")
      (node (ref "C66") (pin "P$1") (pinfunction "1_P$1") (pintype "passive"))
      (node (ref "U3") (pin "31") (pinfunction "VSS1_31") (pintype "power_in"))
    )
    (net (code "65") (name "Net-(C75-1)") (class "Default")
      (node (ref "C75") (pin "P$1") (pinfunction "1_P$1") (pintype "passive"))
      (node (ref "U7") (pin "37") (pinfunction "VCCA_37") (pintype "output"))
    )
    (net (code "66") (name "Net-(C82-2)") (class "Default")
      (node (ref "C82") (pin "P$2") (pinfunction "2_P$2") (pintype "passive"))
      (node (ref "U3") (pin "47") (pinfunction "VSS2_47") (pintype "power_in"))
    )
    (net (code "67") (name "Net-(C95-1)") (class "Default")
      (node (ref "C95") (pin "P$1") (pinfunction "1_P$1") (pintype "passive"))
      (node (ref "U9") (pin "2") (pinfunction "RFOUT_2") (pintype "bidirectional"))
    )
    (net (code "68") (name "Net-(C95-2)") (class "Default")
      (node (ref "C95") (pin "P$2") (pinfunction "2_P$2") (pintype "passive"))
      (node (ref "U10") (pin "27") (pinfunction "LNA_IN1_27") (pintype "bidirectional"))
    )
    (net (code "69") (name "Net-(L4-2)") (class "Default")
      (node (ref "L4") (pin "P$2") (pinfunction "2_P$2") (pintype "passive"))
      (node (ref "U9") (pin "4") (pinfunction "RFIN_4") (pintype "bidirectional"))
    )
    (net (code "70") (name "Net-(R1-1)") (class "Default")
      (node (ref "R1") (pin "P$1") (pinfunction "1_P$1") (pintype "passive"))
      (node (ref "U2") (pin "8") (pinfunction "NPOR_8") (pintype "bidirectional"))
    )
    (net (code "71") (name "Net-(R3-1)") (class "Default")
      (node (ref "R3") (pin "P$1") (pinfunction "1_P$1") (pintype "passive"))
      (node (ref "R6") (pin "P$2") (pinfunction "2_P$2") (pintype "passive"))
      (node (ref "U6") (pin "3") (pinfunction "DI_3") (pintype "input"))
      (node (ref "U7") (pin "43") (pinfunction "EEDATA_43") (pintype "bidirectional"))
    )
    (net (code "72") (name "Net-(R3-2)") (class "Default")
      (node (ref "R3") (pin "P$2") (pinfunction "2_P$2") (pintype "passive"))
      (node (ref "U6") (pin "1") (pinfunction "DO_1") (pintype "output"))
    )
    (net (code "73") (name "Net-(R4-2)") (class "Default")
      (node (ref "R4") (pin "P$2") (pinfunction "2_P$2") (pintype "passive"))
      (node (ref "U6") (pin "5") (pinfunction "CS_5") (pintype "input"))
      (node (ref "U7") (pin "45") (pinfunction "EECS_45") (pintype "bidirectional"))
    )
    (net (code "74") (name "Net-(R5-2)") (class "Default")
      (node (ref "R5") (pin "P$2") (pinfunction "2_P$2") (pintype "passive"))
      (node (ref "U6") (pin "4") (pinfunction "CLK_4") (pintype "input"))
      (node (ref "U7") (pin "44") (pinfunction "EECLK_44") (pintype "output"))
    )
    (net (code "75") (name "Net-(R7-1)") (class "Default")
      (node (ref "R7") (pin "P$1") (pinfunction "1_P$1") (pintype "passive"))
      (node (ref "U7") (pin "5") (pinfunction "REF_5") (pintype "input"))
    )
    (net (code "76") (name "Net-(R9-2)") (class "Default")
      (node (ref "R9") (pin "P$2") (pinfunction "2_P$2") (pintype "passive"))
      (node (ref "U7") (pin "31") (pinfunction "AC7_31") (pintype "bidirectional"))
    )
    (net (code "77") (name "Net-(R10-1)") (class "Default")
      (node (ref "R10") (pin "P$1") (pinfunction "1_P$1") (pintype "passive"))
      (node (ref "U3") (pin "26") (pinfunction "PB0-ADC8/TIM3CH3-TIM1CH2N_26") (pintype "bidirectional"))
    )
    (net (code "78") (name "Net-(R14-1)") (class "Default")
      (node (ref "R14") (pin "P$1") (pinfunction "1_P$1") (pintype "passive"))
      (node (ref "U1") (pin "P14") (pinfunction "SUSPEND_P14") (pintype "input"))
    )
    (net (code "79") (name "Net-(R18-2)") (class "Default")
      (node (ref "R18") (pin "P$2") (pinfunction "2_P$2") (pintype "passive"))
      (node (ref "U1") (pin "C4") (pinfunction "IO_L1P_HSWAPEN_0_C4") (pintype "bidirectional"))
    )
    (net (code "80") (name "Net-(R28-2)") (class "Default")
      (node (ref "LED2") (pin "A") (pinfunction "A_A") (pintype "passive"))
      (node (ref "R28") (pin "P$2") (pinfunction "2_P$2") (pintype "passive"))
    )
    (net (code "81") (name "Net-(R30-1)") (class "Default")
      (node (ref "LED1") (pin "A") (pinfunction "A_A") (pintype "passive"))
      (node (ref "R30") (pin "P$1") (pinfunction "1_P$1") (pintype "passive"))
    )
    (net (code "82") (name "Net-(U2-SW1)") (class "Default")
      (node (ref "L13") (pin "2") (pinfunction "2_2") (pintype "bidirectional"))
      (node (ref "U2") (pin "4") (pinfunction "SW1_4") (pintype "bidirectional"))
    )
    (net (code "83") (name "Net-(U2-SW2)") (class "Default")
      (node (ref "L14") (pin "1") (pinfunction "1_1") (pintype "bidirectional"))
      (node (ref "U2") (pin "7") (pinfunction "SW2_7") (pintype "bidirectional"))
    )
    (net (code "84") (name "Net-(U3-PC3-ADC13)") (class "Default")
      (node (ref "LED2") (pin "C") (pinfunction "C_C") (pintype "passive"))
      (node (ref "U3") (pin "11") (pinfunction "PC3-ADC13_11") (pintype "bidirectional"))
    )
    (net (code "85") (name "Net-(U3-PC4-ADC14)") (class "Default")
      (node (ref "LED1") (pin "C") (pinfunction "C_C") (pintype "passive"))
      (node (ref "U3") (pin "24") (pinfunction "PC4-ADC14_24") (pintype "bidirectional"))
    )
    (net (code "86") (name "Net-(U10A-LNA_OUT)") (class "Default")
      (node (ref "U10") (pin "2") (pinfunction "LNA_OUT_2") (pintype "bidirectional"))
      (node (ref "U8") (pin "1") (pinfunction "RFIN_1") (pintype "bidirectional"))
    )
    (net (code "87") (name "Net-(U10A-MIX_IN)") (class "Default")
      (node (ref "U10") (pin "5") (pinfunction "MIX_IN_5") (pintype "bidirectional"))
      (node (ref "U8") (pin "4") (pinfunction "RFOUT_4") (pintype "bidirectional"))
    )
    (net (code "88") (name "SPI1MISO") (class "Default")
      (node (ref "U1") (pin "A12") (pinfunction "IO_L62N_VREF_0_A12") (pintype "bidirectional"))
      (node (ref "U3") (pin "22") (pinfunction "PA6-SPI1MISO/ADC6/TIM3CH1-TIM1BKIN_22") (pintype "bidirectional"))
    )
    (net (code "89") (name "SPI1MOSI") (class "Default")
      (node (ref "U1") (pin "C11") (pinfunction "IO_L39P_0_C11") (pintype "bidirectional"))
      (node (ref "U3") (pin "23") (pinfunction "PA7-SPI1MOSI/ADC7/TIM3CH2-TIM1CH1N_23") (pintype "bidirectional"))
    )
    (net (code "90") (name "SPI1NSS") (class "Default")
      (node (ref "U1") (pin "A10") (pinfunction "IO_L35N_GCLK16_0_A10") (pintype "bidirectional"))
      (node (ref "U3") (pin "20") (pinfunction "PA4-SPI1NSS/ADC4/USART2CK_20") (pintype "bidirectional"))
    )
    (net (code "91") (name "SPI1SCK") (class "Default")
      (node (ref "U1") (pin "B10") (pinfunction "IO_L35P_GCLK17_0_B10") (pintype "bidirectional"))
      (node (ref "U3") (pin "21") (pinfunction "PA5-SPI1SCK/ADC5_21") (pintype "bidirectional"))
    )
    (net (code "92") (name "SPI2MISO") (class "Default")
      (node (ref "U1") (pin "P10") (pinfunction "IO_L3P_D0_DIN_MISO_MISO1_2_P10") (pintype "bidirectional"))
      (node (ref "U13") (pin "2") (pinfunction "DO_2") (pintype "bidirectional"))
      (node (ref "U3") (pin "35") (pinfunction "PB14-SPI2MISO/USART3RTS/TIM1CH2N_35") (pintype "bidirectional"))
    )
    (net (code "93") (name "SPI2MOSI") (class "Default")
      (node (ref "U1") (pin "T10") (pinfunction "IO_L3N_MOSI_CSI_B_MISO0_2_T10") (pintype "bidirectional"))
      (node (ref "U10") (pin "8") (pinfunction "SDATA_8") (pintype "bidirectional"))
      (node (ref "U13") (pin "5") (pinfunction "DI_5") (pintype "bidirectional"))
      (node (ref "U3") (pin "36") (pinfunction "PB15-SPI2MOSI/TIM1CH3N_36") (pintype "bidirectional"))
    )
    (net (code "94") (name "SPI2NSS_FLASH") (class "Default")
      (node (ref "R13") (pin "P$1") (pinfunction "1_P$1") (pintype "passive"))
      (node (ref "U1") (pin "T3") (pinfunction "IO_L65N_CSO_B_2_T3") (pintype "bidirectional"))
      (node (ref "U13") (pin "1") (pinfunction "NCS_1") (pintype "input"))
      (node (ref "U3") (pin "33") (pinfunction "PB12-SPI2NSS/I2C2SMBAI/USART3CK/TIM1BKIN_33") (pintype "bidirectional"))
    )
    (net (code "95") (name "SPI2NSS_FPGA") (class "Default")
      (node (ref "U3") (pin "10") (pinfunction "PC2-ADC12_10") (pintype "bidirectional"))
    )
    (net (code "96") (name "SPI2NSS_MAX") (class "Default")
      (node (ref "U10") (pin "10") (pinfunction "~{CS}_10") (pintype "bidirectional"))
      (node (ref "U3") (pin "30") (pinfunction "PB11-I2C2SDA/USART3RX-TIM2CH4_30") (pintype "bidirectional"))
    )
    (net (code "97") (name "SPI2SCK") (class "Default")
      (node (ref "U1") (pin "R11") (pinfunction "IO_L1P_CCLK_2_R11") (pintype "bidirectional"))
      (node (ref "U10") (pin "9") (pinfunction "SCLK_9") (pintype "bidirectional"))
      (node (ref "U13") (pin "6") (pinfunction "CLK_6") (pintype "input"))
      (node (ref "U3") (pin "34") (pinfunction "PB13-SPI2SCK/USART3CTS/TIM1CH1N_34") (pintype "bidirectional"))
    )
    (net (code "98") (name "STM_CLK_IN") (class "Default")
      (node (ref "U1") (pin "P9") (pinfunction "IO_L14N_D12_2_P9") (pintype "bidirectional"))
      (node (ref "U3") (pin "5") (pinfunction "PD0-OSC_IN-CANRX_5") (pintype "input"))
    )
    (net (code "99") (name "TIM2CH1ETR") (class "Default")
      (node (ref "U1") (pin "C10") (pinfunction "IO_L37N_GCLK12_0_C10") (pintype "bidirectional"))
      (node (ref "U3") (pin "14") (pinfunction "PA0-WKUP/USART2CTS/ADC0/TIM2CH1ETR_14") (pintype "bidirectional"))
    )
    (net (code "100") (name "TIM2CH2") (class "Default")
      (node (ref "U1") (pin "A9") (pinfunction "IO_L34N_GCLK18_0_A9") (pintype "bidirectional"))
      (node (ref "U3") (pin "15") (pinfunction "PA1-USART2RTS/ADC1/TIM2CH2_15") (pintype "bidirectional"))
    )
    (net (code "101") (name "TIM2CH3") (class "Default")
      (node (ref "U1") (pin "A7") (pinfunction "IO_L6N_0_A7") (pintype "bidirectional"))
      (node (ref "U3") (pin "16") (pinfunction "PA2-USART2TX/ADC2/TIM2CH3_16") (pintype "bidirectional"))
    )
    (net (code "102") (name "TIM2CH4") (class "Default")
      (node (ref "U1") (pin "A5") (pinfunction "IO_L2N_0_A5") (pintype "bidirectional"))
      (node (ref "U3") (pin "17") (pinfunction "PA3-USART2RX/ADC3/TIM2CH4_17") (pintype "bidirectional"))
    )
    (net (code "103") (name "UART1_RX") (class "Default")
      (node (ref "U3") (pin "43") (pinfunction "PA10-USART1RX/TIM1CH3_43") (pintype "bidirectional"))
      (node (ref "X6") (pin "2") (pinfunction "2_2") (pintype "bidirectional"))
    )
    (net (code "104") (name "UART1_TX") (class "Default")
      (node (ref "U3") (pin "42") (pinfunction "PA9-USART1TX/TIM1CH2_42") (pintype "bidirectional"))
      (node (ref "X6") (pin "3") (pinfunction "3_3") (pintype "bidirectional"))
    )
    (net (code "105") (name "UART3_RX") (class "Default")
      (node (ref "U3") (pin "52") (pinfunction "PC11--USART3RX_52") (pintype "bidirectional"))
      (node (ref "X1") (pin "2") (pinfunction "2_2") (pintype "bidirectional"))
    )
    (net (code "106") (name "UART3_TX") (class "Default")
      (node (ref "U3") (pin "51") (pinfunction "PC10--USART3TX_51") (pintype "bidirectional"))
      (node (ref "X1") (pin "3") (pinfunction "3_3") (pintype "bidirectional"))
    )
    (net (code "107") (name "UART6_RX{slash}FTDI_ADBUS0") (class "Default")
      (node (ref "U1") (pin "H15") (pinfunction "IO_L37P_A7_M1A0_1_H15") (pintype "bidirectional"))
      (node (ref "U3") (pin "38") (pinfunction "PC7-TIM3CH2_38") (pintype "bidirectional"))
      (node (ref "U7") (pin "13") (pinfunction "AD0_13") (pintype "bidirectional"))
    )
    (net (code "108") (name "UART6_TX{slash}FTDI_ADBUS1") (class "Default")
      (node (ref "U1") (pin "G16") (pinfunction "IO_L36N_A8_M1BA1_1_G16") (pintype "bidirectional"))
      (node (ref "U3") (pin "37") (pinfunction "PC6-TIM3CH1_37") (pintype "bidirectional"))
      (node (ref "U7") (pin "14") (pinfunction "AD1_14") (pintype "bidirectional"))
    )
    (net (code "109") (name "USB_DM") (class "Default")
      (node (ref "J6") (pin "PIN_2") (pinfunction "2_PIN_2") (pintype "input"))
      (node (ref "U7") (pin "6") (pinfunction "DM_6") (pintype "bidirectional"))
    )
    (net (code "110") (name "USB_DP") (class "Default")
      (node (ref "J6") (pin "PIN_3") (pinfunction "3_PIN_3") (pintype "input"))
      (node (ref "U7") (pin "7") (pinfunction "DP_7") (pintype "bidirectional"))
    )
    (net (code "111") (name "V+") (class "Default")
      (node (ref "D1") (pin "2") (pinfunction "2_2") (pintype "bidirectional"))
      (node (ref "Q1") (pin "3") (pinfunction "D_3") (pintype "passive"))
      (node (ref "X1") (pin "5") (pinfunction "5_5") (pintype "bidirectional"))
      (node (ref "X3") (pin "12") (pinfunction "12_12") (pintype "bidirectional"))
      (node (ref "X6") (pin "5") (pinfunction "5_5") (pintype "bidirectional"))
    )
    (net (code "112") (name "VCC") (class "Default")
      (node (ref "C11") (pin "P$2") (pinfunction "2_P$2") (pintype "passive"))
      (node (ref "C37") (pin "P$1") (pinfunction "1_P$1") (pintype "passive"))
      (node (ref "C39") (pin "P$1") (pinfunction "1_P$1") (pintype "passive"))
      (node (ref "C40") (pin "P$1") (pinfunction "1_P$1") (pintype "passive"))
      (node (ref "C42") (pin "P$1") (pinfunction "1_P$1") (pintype "passive"))
      (node (ref "L2") (pin "P$2") (pinfunction "2_P$2") (pintype "passive"))
      (node (ref "R11") (pin "P$2") (pinfunction "2_P$2") (pintype "passive"))
      (node (ref "U10") (pin "11") (pinfunction "VCCVCO_11") (pintype "bidirectional"))
      (node (ref "U10") (pin "13") (pinfunction "VCCCP_13") (pintype "bidirectional"))
      (node (ref "U10") (pin "23") (pinfunction "VCCIF_23") (pintype "bidirectional"))
      (node (ref "U12") (pin "5") (pinfunction "VOUT_5") (pintype "bidirectional"))
    )
    (net (code "113") (name "VCCINT") (class "Default")
      (node (ref "C10") (pin "P$1") (pinfunction "1_P$1") (pintype "passive"))
      (node (ref "C17") (pin "P$1") (pinfunction "1_P$1") (pintype "passive"))
      (node (ref "C24") (pin "P$1") (pinfunction "1_P$1") (pintype "bidirectional"))
      (node (ref "C28") (pin "P$1") (pinfunction "1_P$1") (pintype "passive"))
      (node (ref "C29") (pin "P$1") (pinfunction "1_P$1") (pintype "passive"))
      (node (ref "C30") (pin "P$1") (pinfunction "1_P$1") (pintype "passive"))
      (node (ref "C31") (pin "P$1") (pinfunction "1_P$1") (pintype "passive"))
      (node (ref "C4") (pin "P$1") (pinfunction "1_P$1") (pintype "passive"))
      (node (ref "C43") (pin "P$1") (pinfunction "1_P$1") (pintype "passive"))
      (node (ref "C46") (pin "P$1") (pinfunction "1_P$1") (pintype "passive"))
      (node (ref "C5") (pin "P$1") (pinfunction "1_P$1") (pintype "passive"))
      (node (ref "C78") (pin "P$1") (pinfunction "1_P$1") (pintype "passive"))
      (node (ref "C80") (pin "P$1") (pinfunction "1_P$1") (pintype "passive"))
      (node (ref "C81") (pin "P$1") (pinfunction "1_P$1") (pintype "passive"))
      (node (ref "L14") (pin "2") (pinfunction "2_2") (pintype "bidirectional"))
      (node (ref "R64") (pin "P$2") (pinfunction "2_P$2") (pintype "passive"))
      (node (ref "U1") (pin "G7") (pinfunction "VCCINT_G7") (pintype "input"))
      (node (ref "U1") (pin "G9") (pinfunction "VCCINT_G9") (pintype "input"))
      (node (ref "U1") (pin "H10") (pinfunction "VCCINT_H10") (pintype "input"))
      (node (ref "U1") (pin "H8") (pinfunction "VCCINT_H8") (pintype "input"))
      (node (ref "U1") (pin "J7") (pinfunction "VCCINT_J7") (pintype "input"))
      (node (ref "U1") (pin "J9") (pinfunction "VCCINT_J9") (pintype "input"))
      (node (ref "U1") (pin "K10") (pinfunction "VCCINT_K10") (pintype "input"))
      (node (ref "U1") (pin "K8") (pinfunction "VCCINT_K8") (pintype "input"))
    )
    (net (code "114") (name "VCCIO") (class "Default")
      (node (ref "C1") (pin "P$2") (pinfunction "2_P$2") (pintype "passive"))
      (node (ref "C107") (pin "P$1") (pinfunction "1_P$1") (pintype "passive"))
      (node (ref "C21") (pin "P$1") (pinfunction "1_P$1") (pintype "bidirectional"))
      (node (ref "C22") (pin "P$1") (pinfunction "1_P$1") (pintype "passive"))
      (node (ref "C23") (pin "P$1") (pinfunction "1_P$1") (pintype "passive"))
      (node (ref "C25") (pin "P$1") (pinfunction "1_P$1") (pintype "bidirectional"))
      (node (ref "C26") (pin "P$1") (pinfunction "1_P$1") (pintype "bidirectional"))
      (node (ref "C27") (pin "P$1") (pinfunction "1_P$1") (pintype "passive"))
      (node (ref "C3") (pin "P$1") (pinfunction "1_P$1") (pintype "passive"))
      (node (ref "C33") (pin "P$2") (pinfunction "2_P$2") (pintype "passive"))
      (node (ref "C44") (pin "P$1") (pinfunction "1_P$1") (pintype "passive"))
      (node (ref "C45") (pin "1") (pinfunction "1_1") (pintype "passive"))
      (node (ref "C48") (pin "P$1") (pinfunction "1_P$1") (pintype "passive"))
      (node (ref "C50") (pin "P$2") (pinfunction "2_P$2") (pintype "passive"))
      (node (ref "C51") (pin "P$2") (pinfunction "2_P$2") (pintype "passive"))
      (node (ref "C52") (pin "P$1") (pinfunction "1_P$1") (pintype "passive"))
      (node (ref "C53") (pin "P$1") (pinfunction "1_P$1") (pintype "passive"))
      (node (ref "C54") (pin "P$1") (pinfunction "1_P$1") (pintype "passive"))
      (node (ref "C55") (pin "P$1") (pinfunction "1_P$1") (pintype "passive"))
      (node (ref "C56") (pin "P$1") (pinfunction "1_P$1") (pintype "passive"))
      (node (ref "C57") (pin "P$2") (pinfunction "2_P$2") (pintype "passive"))
      (node (ref "C58") (pin "P$1") (pinfunction "1_P$1") (pintype "passive"))
      (node (ref "C60") (pin "P$1") (pinfunction "1_P$1") (pintype "passive"))
      (node (ref "C61") (pin "P$1") (pinfunction "1_P$1") (pintype "passive"))
      (node (ref "C62") (pin "P$1") (pinfunction "1_P$1") (pintype "passive"))
      (node (ref "C63") (pin "P$1") (pinfunction "1_P$1") (pintype "passive"))
      (node (ref "C67") (pin "P$1") (pinfunction "1_P$1") (pintype "passive"))
      (node (ref "C69") (pin "1") (pinfunction "1_1") (pintype "passive"))
      (node (ref "C70") (pin "P$1") (pinfunction "1_P$1") (pintype "passive"))
      (node (ref "C71") (pin "P$1") (pinfunction "1_P$1") (pintype "passive"))
      (node (ref "C72") (pin "P$1") (pinfunction "1_P$1") (pintype "passive"))
      (node (ref "C73") (pin "P$1") (pinfunction "1_P$1") (pintype "passive"))
      (node (ref "C74") (pin "P$1") (pinfunction "1_P$1") (pintype "passive"))
      (node (ref "C76") (pin "P$1") (pinfunction "1_P$1") (pintype "passive"))
      (node (ref "C77") (pin "P$1") (pinfunction "1_P$1") (pintype "passive"))
      (node (ref "C8") (pin "P$1") (pinfunction "1_P$1") (pintype "passive"))
      (node (ref "C86") (pin "P$1") (pinfunction "1_P$1") (pintype "bidirectional"))
      (node (ref "C87") (pin "P$1") (pinfunction "1_P$1") (pintype "bidirectional"))
      (node (ref "C96") (pin "P$1") (pinfunction "1_P$1") (pintype "passive"))
      (node (ref "L10") (pin "P$1") (pinfunction "1_P$1") (pintype "passive"))
      (node (ref "L11") (pin "P$1") (pinfunction "1_P$1") (pintype "passive"))
      (node (ref "L13") (pin "1") (pinfunction "1_1") (pintype "bidirectional"))
      (node (ref "R12") (pin "P$2") (pinfunction "2_P$2") (pintype "passive"))
      (node (ref "R13") (pin "P$2") (pinfunction "2_P$2") (pintype "passive"))
      (node (ref "R15") (pin "P$1") (pinfunction "1_P$1") (pintype "passive"))
      (node (ref "R16") (pin "P$2") (pinfunction "2_P$2") (pintype "passive"))
      (node (ref "R17") (pin "P$1") (pinfunction "1_P$1") (pintype "passive"))
      (node (ref "R19") (pin "P$2") (pinfunction "2_P$2") (pintype "passive"))
      (node (ref "R28") (pin "P$1") (pinfunction "1_P$1") (pintype "passive"))
      (node (ref "R30") (pin "P$2") (pinfunction "2_P$2") (pintype "passive"))
      (node (ref "R34") (pin "P$2") (pinfunction "2_P$2") (pintype "passive"))
      (node (ref "R4") (pin "P$1") (pinfunction "1_P$1") (pintype "passive"))
      (node (ref "R5") (pin "P$1") (pinfunction "1_P$1") (pintype "passive"))
      (node (ref "R6") (pin "P$1") (pinfunction "1_P$1") (pintype "passive"))
      (node (ref "R61") (pin "P$2") (pinfunction "2_P$2") (pintype "passive"))
      (node (ref "U1") (pin "B13") (pinfunction "VCCO_0_B13") (pintype "input"))
      (node (ref "U1") (pin "B4") (pinfunction "VCCO_0_B4") (pintype "input"))
      (node (ref "U1") (pin "B9") (pinfunction "VCCO_0_B9") (pintype "input"))
      (node (ref "U1") (pin "D10") (pinfunction "VCCO_0_D10") (pintype "input"))
      (node (ref "U1") (pin "D15") (pinfunction "VCCO_1_D15") (pintype "input"))
      (node (ref "U1") (pin "D2") (pinfunction "VCCO_3_D2") (pintype "input"))
      (node (ref "U1") (pin "D7") (pinfunction "VCCO_0_D7") (pintype "input"))
      (node (ref "U1") (pin "E5") (pinfunction "VCCAUX_E5") (pintype "input"))
      (node (ref "U1") (pin "F11") (pinfunction "VCCAUX_F11") (pintype "input"))
      (node (ref "U1") (pin "F8") (pinfunction "VCCAUX_F8") (pintype "input"))
      (node (ref "U1") (pin "G10") (pinfunction "VCCAUX_G10") (pintype "input"))
      (node (ref "U1") (pin "G13") (pinfunction "VCCO_1_G13") (pintype "input"))
      (node (ref "U1") (pin "G4") (pinfunction "VCCO_3_G4") (pintype "input"))
      (node (ref "U1") (pin "H6") (pinfunction "VCCAUX_H6") (pintype "input"))
      (node (ref "U1") (pin "J10") (pinfunction "VCCAUX_J10") (pintype "input"))
      (node (ref "U1") (pin "J15") (pinfunction "VCCO_1_J15") (pintype "input"))
      (node (ref "U1") (pin "J2") (pinfunction "VCCO_3_J2") (pintype "input"))
      (node (ref "U1") (pin "K13") (pinfunction "VCCO_1_K13") (pintype "input"))
      (node (ref "U1") (pin "K4") (pinfunction "VCCO_3_K4") (pintype "input"))
      (node (ref "U1") (pin "L6") (pinfunction "VCCAUX_L6") (pintype "input"))
      (node (ref "U1") (pin "L9") (pinfunction "VCCAUX_L9") (pintype "input"))
      (node (ref "U1") (pin "N10") (pinfunction "VCCO_2_N10") (pintype "input"))
      (node (ref "U1") (pin "N15") (pinfunction "VCCO_1_N15") (pintype "input"))
      (node (ref "U1") (pin "N2") (pinfunction "VCCO_3_N2") (pintype "input"))
      (node (ref "U1") (pin "N7") (pinfunction "VCCO_2_N7") (pintype "input"))
      (node (ref "U1") (pin "R13") (pinfunction "VCCO_1_R13") (pintype "input"))
      (node (ref "U1") (pin "R4") (pinfunction "VCCO_2_R4") (pintype "input"))
      (node (ref "U1") (pin "R8") (pinfunction "VCCO_2_R8") (pintype "input"))
      (node (ref "U1") (pin "T11") (pinfunction "IO_L1N_M0_CMPMISO_2_T11") (pintype "bidirectional"))
      (node (ref "U10") (pin "14") (pinfunction "VCCD_14") (pintype "bidirectional"))
      (node (ref "U10") (pin "19") (pinfunction "VCCADC_19") (pintype "bidirectional"))
      (node (ref "U13") (pin "3") (pinfunction "NWP_3") (pintype "input"))
      (node (ref "U13") (pin "7") (pinfunction "NHOLD_7") (pintype "input"))
      (node (ref "U13") (pin "8") (pinfunction "VCC_8") (pintype "power_in"))
      (node (ref "U3") (pin "1") (pinfunction "VBAT_1") (pintype "power_in"))
      (node (ref "U3") (pin "13") (pinfunction "VDDA_13") (pintype "power_in"))
      (node (ref "U3") (pin "19") (pinfunction "VDD4_19") (pintype "bidirectional"))
      (node (ref "U3") (pin "32") (pinfunction "VDD1_32") (pintype "power_in"))
      (node (ref "U3") (pin "48") (pinfunction "VDD2_48") (pintype "power_in"))
      (node (ref "U3") (pin "64") (pinfunction "VDD3_64") (pintype "power_in"))
      (node (ref "U4") (pin "4") (pinfunction "VDD_4") (pintype "bidirectional"))
      (node (ref "U6") (pin "6") (pinfunction "VCC_6") (pintype "power_in"))
      (node (ref "U7") (pin "12") (pinfunction "VCCIO1_12") (pintype "power_in"))
      (node (ref "U7") (pin "24") (pinfunction "VCCIO2_24") (pintype "power_in"))
      (node (ref "U7") (pin "39") (pinfunction "VCCD_39") (pintype "bidirectional"))
      (node (ref "U7") (pin "40") (pinfunction "VREGIN_40") (pintype "power_in"))
      (node (ref "U7") (pin "46") (pinfunction "VCCIO3_46") (pintype "power_in"))
      (node (ref "X1") (pin "4") (pinfunction "4_4") (pintype "bidirectional"))
      (node (ref "X5") (pin "1") (pinfunction "1_1") (pintype "bidirectional"))
      (node (ref "X6") (pin "4") (pinfunction "4_4") (pintype "bidirectional"))
    )
    (net (code "115") (name "VDD") (class "Default")
      (node (ref "C2") (pin "P$1") (pinfunction "1_P$1") (pintype "passive"))
      (node (ref "C6") (pin "P$2") (pinfunction "2_P$2") (pintype "passive"))
      (node (ref "Q1") (pin "2") (pinfunction "S_2") (pintype "passive"))
      (node (ref "R1") (pin "P$2") (pinfunction "2_P$2") (pintype "passive"))
      (node (ref "R65") (pin "P$1") (pinfunction "1_P$1") (pintype "passive"))
      (node (ref "U2") (pin "2") (pinfunction "RUN/SS1_2") (pintype "bidirectional"))
      (node (ref "U2") (pin "3") (pinfunction "VIN_3") (pintype "bidirectional"))
      (node (ref "U2") (pin "6") (pinfunction "MODE/SYNC_6") (pintype "bidirectional"))
      (node (ref "U2") (pin "9") (pinfunction "RUN/SS2_9") (pintype "bidirectional"))
    )
    (net (code "116") (name "V_USB") (class "Default")
      (node (ref "D1") (pin "1") (pinfunction "1_1") (pintype "bidirectional"))
      (node (ref "J6") (pin "PIN_1") (pinfunction "1_PIN_1") (pintype "input"))
      (node (ref "R10") (pin "P$2") (pinfunction "2_P$2") (pintype "passive"))
      (node (ref "R8") (pin "P$2") (pinfunction "2_P$2") (pintype "passive"))
      (node (ref "R9") (pin "P$1") (pinfunction "1_P$1") (pintype "passive"))
    )
    (net (code "117") (name "unconnected-(J6-4-PadPIN_4)") (class "Default")
      (node (ref "J6") (pin "PIN_4") (pinfunction "4_PIN_4") (pintype "input"))
    )
    (net (code "118") (name "unconnected-(J6-S1-PadGND_LEFT)") (class "Default")
      (node (ref "J6") (pin "GND_LEFT") (pinfunction "S1_GND_LEFT") (pintype "passive"))
    )
    (net (code "119") (name "unconnected-(J6-S2-PadGND_RIGHT)") (class "Default")
      (node (ref "J6") (pin "GND_RIGHT") (pinfunction "S2_GND_RIGHT") (pintype "passive"))
    )
    (net (code "120") (name "unconnected-(J6-S3-PadGND_UP_LEFT)") (class "Default")
      (node (ref "J6") (pin "GND_UP_LEFT") (pinfunction "S3_GND_UP_LEFT") (pintype "passive"))
    )
    (net (code "121") (name "unconnected-(J6-S4-PadGND_UP_RIGHT)") (class "Default")
      (node (ref "J6") (pin "GND_UP_RIGHT") (pinfunction "S4_GND_UP_RIGHT") (pintype "passive"))
    )
    (net (code "122") (name "unconnected-(U1A-IO_L1N_VREF_0-PadA4)") (class "Default")
      (node (ref "U1") (pin "A4") (pinfunction "IO_L1N_VREF_0_A4") (pintype "bidirectional"))
    )
    (net (code "123") (name "unconnected-(U1A-IO_L2P_0-PadB5)") (class "Default")
      (node (ref "U1") (pin "B5") (pinfunction "IO_L2P_0_B5") (pintype "bidirectional"))
    )
    (net (code "124") (name "unconnected-(U1A-IO_L3N_0-PadC5)") (class "Default")
      (node (ref "U1") (pin "C5") (pinfunction "IO_L3N_0_C5") (pintype "bidirectional"))
    )
    (net (code "125") (name "unconnected-(U1A-IO_L3P_0-PadD5)") (class "Default")
      (node (ref "U1") (pin "D5") (pinfunction "IO_L3P_0_D5") (pintype "bidirectional"))
    )
    (net (code "126") (name "unconnected-(U1A-IO_L4N_0-PadA6)") (class "Default")
      (node (ref "U1") (pin "A6") (pinfunction "IO_L4N_0_A6") (pintype "bidirectional"))
    )
    (net (code "127") (name "unconnected-(U1A-IO_L4P_0-PadB6)") (class "Default")
      (node (ref "U1") (pin "B6") (pinfunction "IO_L4P_0_B6") (pintype "bidirectional"))
    )
    (net (code "128") (name "unconnected-(U1A-IO_L5N_0-PadE6)") (class "Default")
      (node (ref "U1") (pin "E6") (pinfunction "IO_L5N_0_E6") (pintype "bidirectional"))
    )
    (net (code "129") (name "unconnected-(U1A-IO_L5P_0-PadF7)") (class "Default")
      (node (ref "U1") (pin "F7") (pinfunction "IO_L5P_0_F7") (pintype "bidirectional"))
    )
    (net (code "130") (name "unconnected-(U1A-IO_L6P_0-PadC7)") (class "Default")
      (node (ref "U1") (pin "C7") (pinfunction "IO_L6P_0_C7") (pintype "bidirectional"))
    )
    (net (code "131") (name "unconnected-(U1A-IO_L7N_0-PadC6)") (class "Default")
      (node (ref "U1") (pin "C6") (pinfunction "IO_L7N_0_C6") (pintype "bidirectional"))
    )
    (net (code "132") (name "unconnected-(U1A-IO_L7P_0-PadD6)") (class "Default")
      (node (ref "U1") (pin "D6") (pinfunction "IO_L7P_0_D6") (pintype "bidirectional"))
    )
    (net (code "133") (name "unconnected-(U1A-IO_L33N_0-PadA8)") (class "Default")
      (node (ref "U1") (pin "A8") (pinfunction "IO_L33N_0_A8") (pintype "bidirectional"))
    )
    (net (code "134") (name "unconnected-(U1A-IO_L33P_0-PadB8)") (class "Default")
      (node (ref "U1") (pin "B8") (pinfunction "IO_L33P_0_B8") (pintype "bidirectional"))
    )
    (net (code "135") (name "unconnected-(U1A-IO_L34P_GCLK19_0-PadC9)") (class "Default")
      (node (ref "U1") (pin "C9") (pinfunction "IO_L34P_GCLK19_0_C9") (pintype "bidirectional"))
    )
    (net (code "136") (name "unconnected-(U1A-IO_L36N_GCLK14_0-PadE8)") (class "Default")
      (node (ref "U1") (pin "E8") (pinfunction "IO_L36N_GCLK14_0_E8") (pintype "bidirectional"))
    )
    (net (code "137") (name "unconnected-(U1A-IO_L36P_GCLK15_0-PadE7)") (class "Default")
      (node (ref "U1") (pin "E7") (pinfunction "IO_L36P_GCLK15_0_E7") (pintype "bidirectional"))
    )
    (net (code "138") (name "unconnected-(U1A-IO_L37P_GCLK13_0-PadE10)") (class "Default")
      (node (ref "U1") (pin "E10") (pinfunction "IO_L37P_GCLK13_0_E10") (pintype "bidirectional"))
    )
    (net (code "139") (name "unconnected-(U1A-IO_L38N_VREF_0-PadC8)") (class "Default")
      (node (ref "U1") (pin "C8") (pinfunction "IO_L38N_VREF_0_C8") (pintype "bidirectional"))
    )
    (net (code "140") (name "unconnected-(U1A-IO_L38P_0-PadD8)") (class "Default")
      (node (ref "U1") (pin "D8") (pinfunction "IO_L38P_0_D8") (pintype "bidirectional"))
    )
    (net (code "141") (name "unconnected-(U1A-IO_L39N_0-PadA11)") (class "Default")
      (node (ref "U1") (pin "A11") (pinfunction "IO_L39N_0_A11") (pintype "bidirectional"))
    )
    (net (code "142") (name "unconnected-(U1A-IO_L40N_0-PadD9)") (class "Default")
      (node (ref "U1") (pin "D9") (pinfunction "IO_L40N_0_D9") (pintype "bidirectional"))
    )
    (net (code "143") (name "unconnected-(U1A-IO_L40P_0-PadF9)") (class "Default")
      (node (ref "U1") (pin "F9") (pinfunction "IO_L40P_0_F9") (pintype "bidirectional"))
    )
    (net (code "144") (name "unconnected-(U1A-IO_L62P_0-PadB12)") (class "Default")
      (node (ref "U1") (pin "B12") (pinfunction "IO_L62P_0_B12") (pintype "bidirectional"))
    )
    (net (code "145") (name "unconnected-(U1A-IO_L63N_SCP6_0-PadA13)") (class "Default")
      (node (ref "U1") (pin "A13") (pinfunction "IO_L63N_SCP6_0_A13") (pintype "bidirectional"))
    )
    (net (code "146") (name "unconnected-(U1A-IO_L63P_SCP7_0-PadC13)") (class "Default")
      (node (ref "U1") (pin "C13") (pinfunction "IO_L63P_SCP7_0_C13") (pintype "bidirectional"))
    )
    (net (code "147") (name "unconnected-(U1A-IO_L64N_SCP4_0-PadE11)") (class "Default")
      (node (ref "U1") (pin "E11") (pinfunction "IO_L64N_SCP4_0_E11") (pintype "bidirectional"))
    )
    (net (code "148") (name "unconnected-(U1A-IO_L64P_SCP5_0-PadF10)") (class "Default")
      (node (ref "U1") (pin "F10") (pinfunction "IO_L64P_SCP5_0_F10") (pintype "bidirectional"))
    )
    (net (code "149") (name "unconnected-(U1A-IO_L65N_SCP2_0-PadA14)") (class "Default")
      (node (ref "U1") (pin "A14") (pinfunction "IO_L65N_SCP2_0_A14") (pintype "bidirectional"))
    )
    (net (code "150") (name "unconnected-(U1A-IO_L65P_SCP3_0-PadB14)") (class "Default")
      (node (ref "U1") (pin "B14") (pinfunction "IO_L65P_SCP3_0_B14") (pintype "bidirectional"))
    )
    (net (code "151") (name "unconnected-(U1A-IO_L66N_SCP0_0-PadD12)") (class "Default")
      (node (ref "U1") (pin "D12") (pinfunction "IO_L66N_SCP0_0_D12") (pintype "bidirectional"))
    )
    (net (code "152") (name "unconnected-(U1A-IO_L66P_SCP1_0-PadD11)") (class "Default")
      (node (ref "U1") (pin "D11") (pinfunction "IO_L66P_SCP1_0_D11") (pintype "bidirectional"))
    )
    (net (code "153") (name "unconnected-(U1B-IO_L1N_A24_VREF_1-PadE12)") (class "Default")
      (node (ref "U1") (pin "E12") (pinfunction "IO_L1N_A24_VREF_1_E12") (pintype "bidirectional"))
    )
    (net (code "154") (name "unconnected-(U1B-IO_L1P_A25_1-PadE13)") (class "Default")
      (node (ref "U1") (pin "E13") (pinfunction "IO_L1P_A25_1_E13") (pintype "bidirectional"))
    )
    (net (code "155") (name "unconnected-(U1B-IO_L29N_A22_M1A14_1-PadB16)") (class "Default")
      (node (ref "U1") (pin "B16") (pinfunction "IO_L29N_A22_M1A14_1_B16") (pintype "bidirectional"))
    )
    (net (code "156") (name "unconnected-(U1B-IO_L29P_A23_M1A13_1-PadB15)") (class "Default")
      (node (ref "U1") (pin "B15") (pinfunction "IO_L29P_A23_M1A13_1_B15") (pintype "bidirectional"))
    )
    (net (code "157") (name "unconnected-(U1B-IO_L30N_A20_M1A11_1-PadG11)") (class "Default")
      (node (ref "U1") (pin "G11") (pinfunction "IO_L30N_A20_M1A11_1_G11") (pintype "bidirectional"))
    )
    (net (code "158") (name "unconnected-(U1B-IO_L30P_A21_M1RESET_1-PadF12)") (class "Default")
      (node (ref "U1") (pin "F12") (pinfunction "IO_L30P_A21_M1RESET_1_F12") (pintype "bidirectional"))
    )
    (net (code "159") (name "unconnected-(U1B-IO_L31N_A18_M1A12_1-PadD16)") (class "Default")
      (node (ref "U1") (pin "D16") (pinfunction "IO_L31N_A18_M1A12_1_D16") (pintype "bidirectional"))
    )
    (net (code "160") (name "unconnected-(U1B-IO_L31P_A19_M1CKE_1-PadD14)") (class "Default")
      (node (ref "U1") (pin "D14") (pinfunction "IO_L31P_A19_M1CKE_1_D14") (pintype "bidirectional"))
    )
    (net (code "161") (name "unconnected-(U1B-IO_L32N_A16_M1A9_1-PadF14)") (class "Default")
      (node (ref "U1") (pin "F14") (pinfunction "IO_L32N_A16_M1A9_1_F14") (pintype "bidirectional"))
    )
    (net (code "162") (name "unconnected-(U1B-IO_L32P_A17_M1A8_1-PadF13)") (class "Default")
      (node (ref "U1") (pin "F13") (pinfunction "IO_L32P_A17_M1A8_1_F13") (pintype "bidirectional"))
    )
    (net (code "163") (name "unconnected-(U1B-IO_L33N_A14_M1A4_1-PadC16)") (class "Default")
      (node (ref "U1") (pin "C16") (pinfunction "IO_L33N_A14_M1A4_1_C16") (pintype "bidirectional"))
    )
    (net (code "164") (name "unconnected-(U1B-IO_L33P_A15_M1A10_1-PadC15)") (class "Default")
      (node (ref "U1") (pin "C15") (pinfunction "IO_L33P_A15_M1A10_1_C15") (pintype "bidirectional"))
    )
    (net (code "165") (name "unconnected-(U1B-IO_L36P_A9_M1BA0_1-PadG14)") (class "Default")
      (node (ref "U1") (pin "G14") (pinfunction "IO_L36P_A9_M1BA0_1_G14") (pintype "bidirectional"))
    )
    (net (code "166") (name "unconnected-(U1B-IO_L37N_A6_M1A1_1-PadH16)") (class "Default")
      (node (ref "U1") (pin "H16") (pinfunction "IO_L37N_A6_M1A1_1_H16") (pintype "bidirectional"))
    )
    (net (code "167") (name "unconnected-(U1B-IO_L38N_A4_M1CLKN_1-PadH11)") (class "Default")
      (node (ref "U1") (pin "H11") (pinfunction "IO_L38N_A4_M1CLKN_1_H11") (pintype "bidirectional"))
    )
    (net (code "168") (name "unconnected-(U1B-IO_L38P_A5_M1CLK_1-PadG12)") (class "Default")
      (node (ref "U1") (pin "G12") (pinfunction "IO_L38P_A5_M1CLK_1_G12") (pintype "bidirectional"))
    )
    (net (code "169") (name "unconnected-(U1B-IO_L39N_M1ODT_1-PadH14)") (class "Default")
      (node (ref "U1") (pin "H14") (pinfunction "IO_L39N_M1ODT_1_H14") (pintype "bidirectional"))
    )
    (net (code "170") (name "unconnected-(U1B-IO_L39P_M1A3_1-PadH13)") (class "Default")
      (node (ref "U1") (pin "H13") (pinfunction "IO_L39P_M1A3_1_H13") (pintype "bidirectional"))
    )
    (net (code "171") (name "unconnected-(U1B-IO_L40N_GCLK10_M1A6_1-PadJ12)") (class "Default")
      (node (ref "U1") (pin "J12") (pinfunction "IO_L40N_GCLK10_M1A6_1_J12") (pintype "bidirectional"))
    )
    (net (code "172") (name "unconnected-(U1B-IO_L40P_GCLK11_M1A5_1-PadJ11)") (class "Default")
      (node (ref "U1") (pin "J11") (pinfunction "IO_L40P_GCLK11_M1A5_1_J11") (pintype "bidirectional"))
    )
    (net (code "173") (name "unconnected-(U1B-IO_L41P_GCLK9_IRDY1_M1RASN_1-PadJ13)") (class "Default")
      (node (ref "U1") (pin "J13") (pinfunction "IO_L41P_GCLK9_IRDY1_M1RASN_1_J13") (pintype "bidirectional"))
    )
    (net (code "174") (name "unconnected-(U1B-IO_L42N_GCLK6_TRDY1_M1LDM_1-PadK11)") (class "Default")
      (node (ref "U1") (pin "K11") (pinfunction "IO_L42N_GCLK6_TRDY1_M1LDM_1_K11") (pintype "bidirectional"))
    )
    (net (code "175") (name "unconnected-(U1B-IO_L42P_GCLK7_M1UDM_1-PadK12)") (class "Default")
      (node (ref "U1") (pin "K12") (pinfunction "IO_L42P_GCLK7_M1UDM_1_K12") (pintype "bidirectional"))
    )
    (net (code "176") (name "unconnected-(U1B-IO_L43N_GCLK4_M1DQ5_1-PadJ16)") (class "Default")
      (node (ref "U1") (pin "J16") (pinfunction "IO_L43N_GCLK4_M1DQ5_1_J16") (pintype "bidirectional"))
    )
    (net (code "177") (name "unconnected-(U1B-IO_L48P_HDC_M1DQ8_1-PadP15)") (class "Default")
      (node (ref "U1") (pin "P15") (pinfunction "IO_L48P_HDC_M1DQ8_1_P15") (pintype "bidirectional"))
    )
    (net (code "178") (name "unconnected-(U1B-IO_L49N_M1DQ11_1-PadR16)") (class "Default")
      (node (ref "U1") (pin "R16") (pinfunction "IO_L49N_M1DQ11_1_R16") (pintype "bidirectional"))
    )
    (net (code "179") (name "unconnected-(U1B-IO_L50P_M1UDQS_1-PadR14)") (class "Default")
      (node (ref "U1") (pin "R14") (pinfunction "IO_L50P_M1UDQS_1_R14") (pintype "bidirectional"))
    )
    (net (code "180") (name "unconnected-(U1B-IO_L51N_M1DQ13_1-PadT13)") (class "Default")
      (node (ref "U1") (pin "T13") (pinfunction "IO_L51N_M1DQ13_1_T13") (pintype "bidirectional"))
    )
    (net (code "181") (name "unconnected-(U1B-IO_L51P_M1DQ12_1-PadT14)") (class "Default")
      (node (ref "U1") (pin "T14") (pinfunction "IO_L51P_M1DQ12_1_T14") (pintype "bidirectional"))
    )
    (net (code "182") (name "unconnected-(U1B-IO_L52N_M1DQ15_1-PadT12)") (class "Default")
      (node (ref "U1") (pin "T12") (pinfunction "IO_L52N_M1DQ15_1_T12") (pintype "bidirectional"))
    )
    (net (code "183") (name "unconnected-(U1B-IO_L52P_M1DQ14_1-PadR12)") (class "Default")
      (node (ref "U1") (pin "R12") (pinfunction "IO_L52P_M1DQ14_1_R12") (pintype "bidirectional"))
    )
    (net (code "184") (name "unconnected-(U1B-IO_L53N_VREF_1-PadL13)") (class "Default")
      (node (ref "U1") (pin "L13") (pinfunction "IO_L53N_VREF_1_L13") (pintype "bidirectional"))
    )
    (net (code "185") (name "unconnected-(U1B-IO_L53P_1-PadL12)") (class "Default")
      (node (ref "U1") (pin "L12") (pinfunction "IO_L53P_1_L12") (pintype "bidirectional"))
    )
    (net (code "186") (name "unconnected-(U1B-IO_L74P_AWAKE_1-PadM13)") (class "Default")
      (node (ref "U1") (pin "M13") (pinfunction "IO_L74P_AWAKE_1_M13") (pintype "bidirectional"))
    )
    (net (code "187") (name "unconnected-(U1C-CMPCS_B_2-PadL11)") (class "Default")
      (node (ref "U1") (pin "L11") (pinfunction "CMPCS_B_2_L11") (pintype "bidirectional"))
    )
    (net (code "188") (name "unconnected-(U1C-IO_L2N_CMPMOSI_2-PadM11)") (class "Default")
      (node (ref "U1") (pin "M11") (pinfunction "IO_L2N_CMPMOSI_2_M11") (pintype "bidirectional"))
    )
    (net (code "189") (name "unconnected-(U1C-IO_L2P_CMPCLK_2-PadM12)") (class "Default")
      (node (ref "U1") (pin "M12") (pinfunction "IO_L2P_CMPCLK_2_M12") (pintype "bidirectional"))
    )
    (net (code "190") (name "unconnected-(U1C-IO_L12N_D2_MISO3_2-PadP12)") (class "Default")
      (node (ref "U1") (pin "P12") (pinfunction "IO_L12N_D2_MISO3_2_P12") (pintype "bidirectional"))
    )
    (net (code "191") (name "unconnected-(U1C-IO_L12P_D1_MISO2_2-PadN12)") (class "Default")
      (node (ref "U1") (pin "N12") (pinfunction "IO_L12P_D1_MISO2_2_N12") (pintype "bidirectional"))
    )
    (net (code "192") (name "unconnected-(U1C-IO_L13N_D10_2-PadP11)") (class "Default")
      (node (ref "U1") (pin "P11") (pinfunction "IO_L13N_D10_2_P11") (pintype "bidirectional"))
    )
    (net (code "193") (name "unconnected-(U1C-IO_L14P_D11_2-PadN9)") (class "Default")
      (node (ref "U1") (pin "N9") (pinfunction "IO_L14P_D11_2_N9") (pintype "bidirectional"))
    )
    (net (code "194") (name "unconnected-(U1C-IO_L16N_VREF_2-PadM10)") (class "Default")
      (node (ref "U1") (pin "M10") (pinfunction "IO_L16N_VREF_2_M10") (pintype "bidirectional"))
    )
    (net (code "195") (name "unconnected-(U1C-IO_L16P_2-PadL10)") (class "Default")
      (node (ref "U1") (pin "L10") (pinfunction "IO_L16P_2_L10") (pintype "bidirectional"))
    )
    (net (code "196") (name "unconnected-(U1C-IO_L23N_2-PadT9)") (class "Default")
      (node (ref "U1") (pin "T9") (pinfunction "IO_L23N_2_T9") (pintype "bidirectional"))
    )
    (net (code "197") (name "unconnected-(U1C-IO_L23P_2-PadR9)") (class "Default")
      (node (ref "U1") (pin "R9") (pinfunction "IO_L23P_2_R9") (pintype "bidirectional"))
    )
    (net (code "198") (name "unconnected-(U1C-IO_L29N_GCLK2_2-PadN8)") (class "Default")
      (node (ref "U1") (pin "N8") (pinfunction "IO_L29N_GCLK2_2_N8") (pintype "bidirectional"))
    )
    (net (code "199") (name "unconnected-(U1C-IO_L29P_GCLK3_2-PadM9)") (class "Default")
      (node (ref "U1") (pin "M9") (pinfunction "IO_L29P_GCLK3_2_M9") (pintype "bidirectional"))
    )
    (net (code "200") (name "unconnected-(U1C-IO_L30N_GCLK0_USERCCLK_2-PadT8)") (class "Default")
      (node (ref "U1") (pin "T8") (pinfunction "IO_L30N_GCLK0_USERCCLK_2_T8") (pintype "bidirectional"))
    )
    (net (code "201") (name "unconnected-(U1C-IO_L30P_GCLK1_D13_2-PadP8)") (class "Default")
      (node (ref "U1") (pin "P8") (pinfunction "IO_L30P_GCLK1_D13_2_P8") (pintype "bidirectional"))
    )
    (net (code "202") (name "unconnected-(U1C-IO_L31N_GCLK30_D15_2-PadM7)") (class "Default")
      (node (ref "U1") (pin "M7") (pinfunction "IO_L31N_GCLK30_D15_2_M7") (pintype "bidirectional"))
    )
    (net (code "203") (name "unconnected-(U1C-IO_L31P_GCLK31_D14_2-PadP7)") (class "Default")
      (node (ref "U1") (pin "P7") (pinfunction "IO_L31P_GCLK31_D14_2_P7") (pintype "bidirectional"))
    )
    (net (code "204") (name "unconnected-(U1C-IO_L32N_GCLK28_2-PadT7)") (class "Default")
      (node (ref "U1") (pin "T7") (pinfunction "IO_L32N_GCLK28_2_T7") (pintype "bidirectional"))
    )
    (net (code "205") (name "unconnected-(U1C-IO_L32P_GCLK29_2-PadR7)") (class "Default")
      (node (ref "U1") (pin "R7") (pinfunction "IO_L32P_GCLK29_2_R7") (pintype "bidirectional"))
    )
    (net (code "206") (name "unconnected-(U1C-IO_L47N_2-PadT6)") (class "Default")
      (node (ref "U1") (pin "T6") (pinfunction "IO_L47N_2_T6") (pintype "bidirectional"))
    )
    (net (code "207") (name "unconnected-(U1C-IO_L47P_2-PadP6)") (class "Default")
      (node (ref "U1") (pin "P6") (pinfunction "IO_L47P_2_P6") (pintype "bidirectional"))
    )
    (net (code "208") (name "unconnected-(U1C-IO_L48N_RDWR_B_VREF_2-PadT5)") (class "Default")
      (node (ref "U1") (pin "T5") (pinfunction "IO_L48N_RDWR_B_VREF_2_T5") (pintype "bidirectional"))
    )
    (net (code "209") (name "unconnected-(U1C-IO_L48P_D7_2-PadR5)") (class "Default")
      (node (ref "U1") (pin "R5") (pinfunction "IO_L48P_D7_2_R5") (pintype "bidirectional"))
    )
    (net (code "210") (name "unconnected-(U1C-IO_L49N_D4_2-PadP5)") (class "Default")
      (node (ref "U1") (pin "P5") (pinfunction "IO_L49N_D4_2_P5") (pintype "bidirectional"))
    )
    (net (code "211") (name "unconnected-(U1C-IO_L49P_D3_2-PadN5)") (class "Default")
      (node (ref "U1") (pin "N5") (pinfunction "IO_L49P_D3_2_N5") (pintype "bidirectional"))
    )
    (net (code "212") (name "unconnected-(U1C-IO_L62N_D6_2-PadL7)") (class "Default")
      (node (ref "U1") (pin "L7") (pinfunction "IO_L62N_D6_2_L7") (pintype "bidirectional"))
    )
    (net (code "213") (name "unconnected-(U1C-IO_L62P_D5_2-PadL8)") (class "Default")
      (node (ref "U1") (pin "L8") (pinfunction "IO_L62P_D5_2_L8") (pintype "bidirectional"))
    )
    (net (code "214") (name "unconnected-(U1C-IO_L63N_2-PadT4)") (class "Default")
      (node (ref "U1") (pin "T4") (pinfunction "IO_L63N_2_T4") (pintype "bidirectional"))
    )
    (net (code "215") (name "unconnected-(U1C-IO_L63P_2-PadP4)") (class "Default")
      (node (ref "U1") (pin "P4") (pinfunction "IO_L63P_2_P4") (pintype "bidirectional"))
    )
    (net (code "216") (name "unconnected-(U1C-IO_L64N_D9_2-PadN6)") (class "Default")
      (node (ref "U1") (pin "N6") (pinfunction "IO_L64N_D9_2_N6") (pintype "bidirectional"))
    )
    (net (code "217") (name "unconnected-(U1C-IO_L64P_D8_2-PadM6)") (class "Default")
      (node (ref "U1") (pin "M6") (pinfunction "IO_L64P_D8_2_M6") (pintype "bidirectional"))
    )
    (net (code "218") (name "unconnected-(U1D-IO_L1N_VREF_3-PadM3)") (class "Default")
      (node (ref "U1") (pin "M3") (pinfunction "IO_L1N_VREF_3_M3") (pintype "bidirectional"))
    )
    (net (code "219") (name "unconnected-(U1D-IO_L1P_3-PadM4)") (class "Default")
      (node (ref "U1") (pin "M4") (pinfunction "IO_L1P_3_M4") (pintype "bidirectional"))
    )
    (net (code "220") (name "unconnected-(U1D-IO_L2N_3-PadN4)") (class "Default")
      (node (ref "U1") (pin "N4") (pinfunction "IO_L2N_3_N4") (pintype "bidirectional"))
    )
    (net (code "221") (name "unconnected-(U1D-IO_L2P_3-PadM5)") (class "Default")
      (node (ref "U1") (pin "M5") (pinfunction "IO_L2P_3_M5") (pintype "bidirectional"))
    )
    (net (code "222") (name "unconnected-(U1D-IO_L32P_M3DQ14_3-PadR2)") (class "Default")
      (node (ref "U1") (pin "R2") (pinfunction "IO_L32P_M3DQ14_3_R2") (pintype "bidirectional"))
    )
    (net (code "223") (name "unconnected-(U1D-IO_L33N_M3DQ13_3-PadP1)") (class "Default")
      (node (ref "U1") (pin "P1") (pinfunction "IO_L33N_M3DQ13_3_P1") (pintype "bidirectional"))
    )
    (net (code "224") (name "unconnected-(U1D-IO_L33P_M3DQ12_3-PadP2)") (class "Default")
      (node (ref "U1") (pin "P2") (pinfunction "IO_L33P_M3DQ12_3_P2") (pintype "bidirectional"))
    )
    (net (code "225") (name "unconnected-(U1D-IO_L34P_M3UDQS_3-PadN3)") (class "Default")
      (node (ref "U1") (pin "N3") (pinfunction "IO_L34P_M3UDQS_3_N3") (pintype "bidirectional"))
    )
    (net (code "226") (name "unconnected-(U1D-IO_L35P_M3DQ10_3-PadM2)") (class "Default")
      (node (ref "U1") (pin "M2") (pinfunction "IO_L35P_M3DQ10_3_M2") (pintype "bidirectional"))
    )
    (net (code "227") (name "unconnected-(U1D-IO_L36P_M3DQ8_3-PadL3)") (class "Default")
      (node (ref "U1") (pin "L3") (pinfunction "IO_L36P_M3DQ8_3_L3") (pintype "bidirectional"))
    )
    (net (code "228") (name "unconnected-(U1D-IO_L37N_M3DQ1_3-PadK1)") (class "Default")
      (node (ref "U1") (pin "K1") (pinfunction "IO_L37N_M3DQ1_3_K1") (pintype "bidirectional"))
    )
    (net (code "229") (name "unconnected-(U1D-IO_L37P_M3DQ0_3-PadK2)") (class "Default")
      (node (ref "U1") (pin "K2") (pinfunction "IO_L37P_M3DQ0_3_K2") (pintype "bidirectional"))
    )
    (net (code "230") (name "unconnected-(U1D-IO_L38P_M3DQ2_3-PadJ3)") (class "Default")
      (node (ref "U1") (pin "J3") (pinfunction "IO_L38P_M3DQ2_3_J3") (pintype "bidirectional"))
    )
    (net (code "231") (name "unconnected-(U1D-IO_L39N_M3LDQSN_3-PadH1)") (class "Default")
      (node (ref "U1") (pin "H1") (pinfunction "IO_L39N_M3LDQSN_3_H1") (pintype "bidirectional"))
    )
    (net (code "232") (name "unconnected-(U1D-IO_L39P_M3LDQS_3-PadH2)") (class "Default")
      (node (ref "U1") (pin "H2") (pinfunction "IO_L39P_M3LDQS_3_H2") (pintype "bidirectional"))
    )
    (net (code "233") (name "unconnected-(U1D-IO_L40N_M3DQ7_3-PadG1)") (class "Default")
      (node (ref "U1") (pin "G1") (pinfunction "IO_L40N_M3DQ7_3_G1") (pintype "bidirectional"))
    )
    (net (code "234") (name "unconnected-(U1D-IO_L40P_M3DQ6_3-PadG3)") (class "Default")
      (node (ref "U1") (pin "G3") (pinfunction "IO_L40P_M3DQ6_3_G3") (pintype "bidirectional"))
    )
    (net (code "235") (name "unconnected-(U1D-IO_L41P_GCLK27_M3DQ4_3-PadF2)") (class "Default")
      (node (ref "U1") (pin "F2") (pinfunction "IO_L41P_GCLK27_M3DQ4_3_F2") (pintype "bidirectional"))
    )
    (net (code "236") (name "unconnected-(U1D-IO_L42N_GCLK24_M3LDM_3-PadJ4)") (class "Default")
      (node (ref "U1") (pin "J4") (pinfunction "IO_L42N_GCLK24_M3LDM_3_J4") (pintype "bidirectional"))
    )
    (net (code "237") (name "unconnected-(U1D-IO_L42P_GCLK25_TRDY2_M3UDM_3-PadK3)") (class "Default")
      (node (ref "U1") (pin "K3") (pinfunction "IO_L42P_GCLK25_TRDY2_M3UDM_3_K3") (pintype "bidirectional"))
    )
    (net (code "238") (name "unconnected-(U1D-IO_L43N_GCLK22_IRDY2_M3CASN_3-PadH5)") (class "Default")
      (node (ref "U1") (pin "H5") (pinfunction "IO_L43N_GCLK22_IRDY2_M3CASN_3_H5") (pintype "bidirectional"))
    )
    (net (code "239") (name "unconnected-(U1D-IO_L43P_GCLK23_M3RASN_3-PadJ6)") (class "Default")
      (node (ref "U1") (pin "J6") (pinfunction "IO_L43P_GCLK23_M3RASN_3_J6") (pintype "bidirectional"))
    )
    (net (code "240") (name "unconnected-(U1D-IO_L44P_GCLK21_M3A5_3-PadH4)") (class "Default")
      (node (ref "U1") (pin "H4") (pinfunction "IO_L44P_GCLK21_M3A5_3_H4") (pintype "bidirectional"))
    )
    (net (code "241") (name "unconnected-(U1D-IO_L45N_M3ODT_3-PadL5)") (class "Default")
      (node (ref "U1") (pin "L5") (pinfunction "IO_L45N_M3ODT_3_L5") (pintype "bidirectional"))
    )
    (net (code "242") (name "unconnected-(U1D-IO_L45P_M3A3_3-PadL4)") (class "Default")
      (node (ref "U1") (pin "L4") (pinfunction "IO_L45P_M3A3_3_L4") (pintype "bidirectional"))
    )
    (net (code "243") (name "unconnected-(U1D-IO_L46P_M3CLK_3-PadE2)") (class "Default")
      (node (ref "U1") (pin "E2") (pinfunction "IO_L46P_M3CLK_3_E2") (pintype "bidirectional"))
    )
    (net (code "244") (name "unconnected-(U1D-IO_L47N_M3A1_3-PadK6)") (class "Default")
      (node (ref "U1") (pin "K6") (pinfunction "IO_L47N_M3A1_3_K6") (pintype "bidirectional"))
    )
    (net (code "245") (name "unconnected-(U1D-IO_L47P_M3A0_3-PadK5)") (class "Default")
      (node (ref "U1") (pin "K5") (pinfunction "IO_L47P_M3A0_3_K5") (pintype "bidirectional"))
    )
    (net (code "246") (name "unconnected-(U1D-IO_L48N_M3BA1_3-PadC2)") (class "Default")
      (node (ref "U1") (pin "C2") (pinfunction "IO_L48N_M3BA1_3_C2") (pintype "bidirectional"))
    )
    (net (code "247") (name "unconnected-(U1D-IO_L48P_M3BA0_3-PadC3)") (class "Default")
      (node (ref "U1") (pin "C3") (pinfunction "IO_L48P_M3BA0_3_C3") (pintype "bidirectional"))
    )
    (net (code "248") (name "unconnected-(U1D-IO_L49P_M3A7_3-PadD3)") (class "Default")
      (node (ref "U1") (pin "D3") (pinfunction "IO_L49P_M3A7_3_D3") (pintype "bidirectional"))
    )
    (net (code "249") (name "unconnected-(U1D-IO_L50N_M3BA2_3-PadB1)") (class "Default")
      (node (ref "U1") (pin "B1") (pinfunction "IO_L50N_M3BA2_3_B1") (pintype "bidirectional"))
    )
    (net (code "250") (name "unconnected-(U1D-IO_L51N_M3A4_3-PadG5)") (class "Default")
      (node (ref "U1") (pin "G5") (pinfunction "IO_L51N_M3A4_3_G5") (pintype "bidirectional"))
    )
    (net (code "251") (name "unconnected-(U1D-IO_L51P_M3A10_3-PadG6)") (class "Default")
      (node (ref "U1") (pin "G6") (pinfunction "IO_L51P_M3A10_3_G6") (pintype "bidirectional"))
    )
    (net (code "252") (name "unconnected-(U1D-IO_L52N_M3A9_3-PadA2)") (class "Default")
      (node (ref "U1") (pin "A2") (pinfunction "IO_L52N_M3A9_3_A2") (pintype "bidirectional"))
    )
    (net (code "253") (name "unconnected-(U1D-IO_L52P_M3A8_3-PadB2)") (class "Default")
      (node (ref "U1") (pin "B2") (pinfunction "IO_L52P_M3A8_3_B2") (pintype "bidirectional"))
    )
    (net (code "254") (name "unconnected-(U1D-IO_L53N_M3A12_3-PadF3)") (class "Default")
      (node (ref "U1") (pin "F3") (pinfunction "IO_L53N_M3A12_3_F3") (pintype "bidirectional"))
    )
    (net (code "255") (name "unconnected-(U1D-IO_L53P_M3CKE_3-PadF4)") (class "Default")
      (node (ref "U1") (pin "F4") (pinfunction "IO_L53P_M3CKE_3_F4") (pintype "bidirectional"))
    )
    (net (code "256") (name "unconnected-(U1D-IO_L54N_M3A11_3-PadE3)") (class "Default")
      (node (ref "U1") (pin "E3") (pinfunction "IO_L54N_M3A11_3_E3") (pintype "bidirectional"))
    )
    (net (code "257") (name "unconnected-(U1D-IO_L54P_M3RESET_3-PadE4)") (class "Default")
      (node (ref "U1") (pin "E4") (pinfunction "IO_L54P_M3RESET_3_E4") (pintype "bidirectional"))
    )
    (net (code "258") (name "unconnected-(U1D-IO_L55N_M3A14_3-PadF5)") (class "Default")
      (node (ref "U1") (pin "F5") (pinfunction "IO_L55N_M3A14_3_F5") (pintype "bidirectional"))
    )
    (net (code "259") (name "unconnected-(U1D-IO_L55P_M3A13_3-PadF6)") (class "Default")
      (node (ref "U1") (pin "F6") (pinfunction "IO_L55P_M3A13_3_F6") (pintype "bidirectional"))
    )
    (net (code "260") (name "unconnected-(U1D-IO_L83N_VREF_3-PadA3)") (class "Default")
      (node (ref "U1") (pin "A3") (pinfunction "IO_L83N_VREF_3_A3") (pintype "bidirectional"))
    )
    (net (code "261") (name "unconnected-(U1D-IO_L83P_3-PadB3)") (class "Default")
      (node (ref "U1") (pin "B3") (pinfunction "IO_L83P_3_B3") (pintype "bidirectional"))
    )
    (net (code "262") (name "unconnected-(U3-PA11-USART1CTS{slash}CANRX{slash}USBDM{slash}TIM1CH4-Pad44)") (class "Default")
      (node (ref "U3") (pin "44") (pinfunction "PA11-USART1CTS/CANRX/USBDM/TIM1CH4_44") (pintype "bidirectional"))
    )
    (net (code "263") (name "unconnected-(U3-PA12-USART1RTS{slash}CANTX{slash}USBDP{slash}TIM1ETR-Pad45)") (class "Default")
      (node (ref "U3") (pin "45") (pinfunction "PA12-USART1RTS/CANTX/USBDP/TIM1ETR_45") (pintype "bidirectional"))
    )
    (net (code "264") (name "unconnected-(U3-PB2{slash}BOOT1-Pad28)") (class "Default")
      (node (ref "U3") (pin "28") (pinfunction "PB2/BOOT1_28") (pintype "bidirectional"))
    )
    (net (code "265") (name "unconnected-(U3-PB4{slash}JNTRST--TIM3CH1{slash}SPI1MISO-Pad56)") (class "Default")
      (node (ref "U3") (pin "56") (pinfunction "PB4/JNTRST--TIM3CH1/SPI1MISO_56") (pintype "bidirectional"))
    )
    (net (code "266") (name "unconnected-(U3-PB5-I2C1SMBAI-TIM3CH2{slash}SPI1MOSI-Pad57)") (class "Default")
      (node (ref "U3") (pin "57") (pinfunction "PB5-I2C1SMBAI-TIM3CH2/SPI1MOSI_57") (pintype "bidirectional"))
    )
    (net (code "267") (name "unconnected-(U3-PB6-I2C1SCL{slash}TIM4CH1-USART1TX-Pad58)") (class "Default")
      (node (ref "U3") (pin "58") (pinfunction "PB6-I2C1SCL/TIM4CH1-USART1TX_58") (pintype "bidirectional"))
    )
    (net (code "268") (name "unconnected-(U3-PB7-I2C1SDA{slash}TIM4CH2-USART1RX-Pad59)") (class "Default")
      (node (ref "U3") (pin "59") (pinfunction "PB7-I2C1SDA/TIM4CH2-USART1RX_59") (pintype "bidirectional"))
    )
    (net (code "269") (name "unconnected-(U3-PC8-TIM3CH3-Pad39)") (class "Default")
      (node (ref "U3") (pin "39") (pinfunction "PC8-TIM3CH3_39") (pintype "bidirectional"))
    )
    (net (code "270") (name "unconnected-(U3-PC9-TIM3CH4-Pad40)") (class "Default")
      (node (ref "U3") (pin "40") (pinfunction "PC9-TIM3CH4_40") (pintype "bidirectional"))
    )
    (net (code "271") (name "unconnected-(U3-PC13-TAMPER-RTC-Pad2)") (class "Default")
      (node (ref "U3") (pin "2") (pinfunction "PC13-TAMPER-RTC_2") (pintype "bidirectional"))
    )
    (net (code "272") (name "unconnected-(U3-PC14-OSC32_IN-Pad3)") (class "Default")
      (node (ref "U3") (pin "3") (pinfunction "PC14-OSC32_IN_3") (pintype "bidirectional"))
    )
    (net (code "273") (name "unconnected-(U3-PC15-OSC32_OUT-Pad4)") (class "Default")
      (node (ref "U3") (pin "4") (pinfunction "PC15-OSC32_OUT_4") (pintype "bidirectional"))
    )
    (net (code "274") (name "unconnected-(U3-PD1-OSC_OUT-CANTX-Pad6)") (class "Default")
      (node (ref "U3") (pin "6") (pinfunction "PD1-OSC_OUT-CANTX_6") (pintype "output"))
    )
    (net (code "275") (name "unconnected-(U3-PD2-TIM3ETR-Pad54)") (class "Default")
      (node (ref "U3") (pin "54") (pinfunction "PD2-TIM3ETR_54") (pintype "bidirectional"))
    )
    (net (code "276") (name "unconnected-(U7-AC8-Pad32)") (class "Default")
      (node (ref "U7") (pin "32") (pinfunction "AC8_32") (pintype "bidirectional"))
    )
    (net (code "277") (name "unconnected-(U7-AC9-Pad33)") (class "Default")
      (node (ref "U7") (pin "33") (pinfunction "AC9_33") (pintype "bidirectional"))
    )
    (net (code "278") (name "unconnected-(U10C-NC1-Pad22)") (class "Default")
      (node (ref "U10") (pin "22") (pinfunction "NC1_22") (pintype "bidirectional"))
    )
    (net (code "279") (name "unconnected-(U10C-NC2-Pad28)") (class "Default")
      (node (ref "U10") (pin "28") (pinfunction "NC2_28") (pintype "bidirectional"))
    )
    (net (code "280") (name "unconnected-(U12-NC-Pad4)") (class "Default")
      (node (ref "U12") (pin "4") (pinfunction "NC_4") (pintype "bidirectional"))
    )
  )
)
